# DSKY_control_circuitry.net
KiCad netlist of a schematic drawn in EAGLE
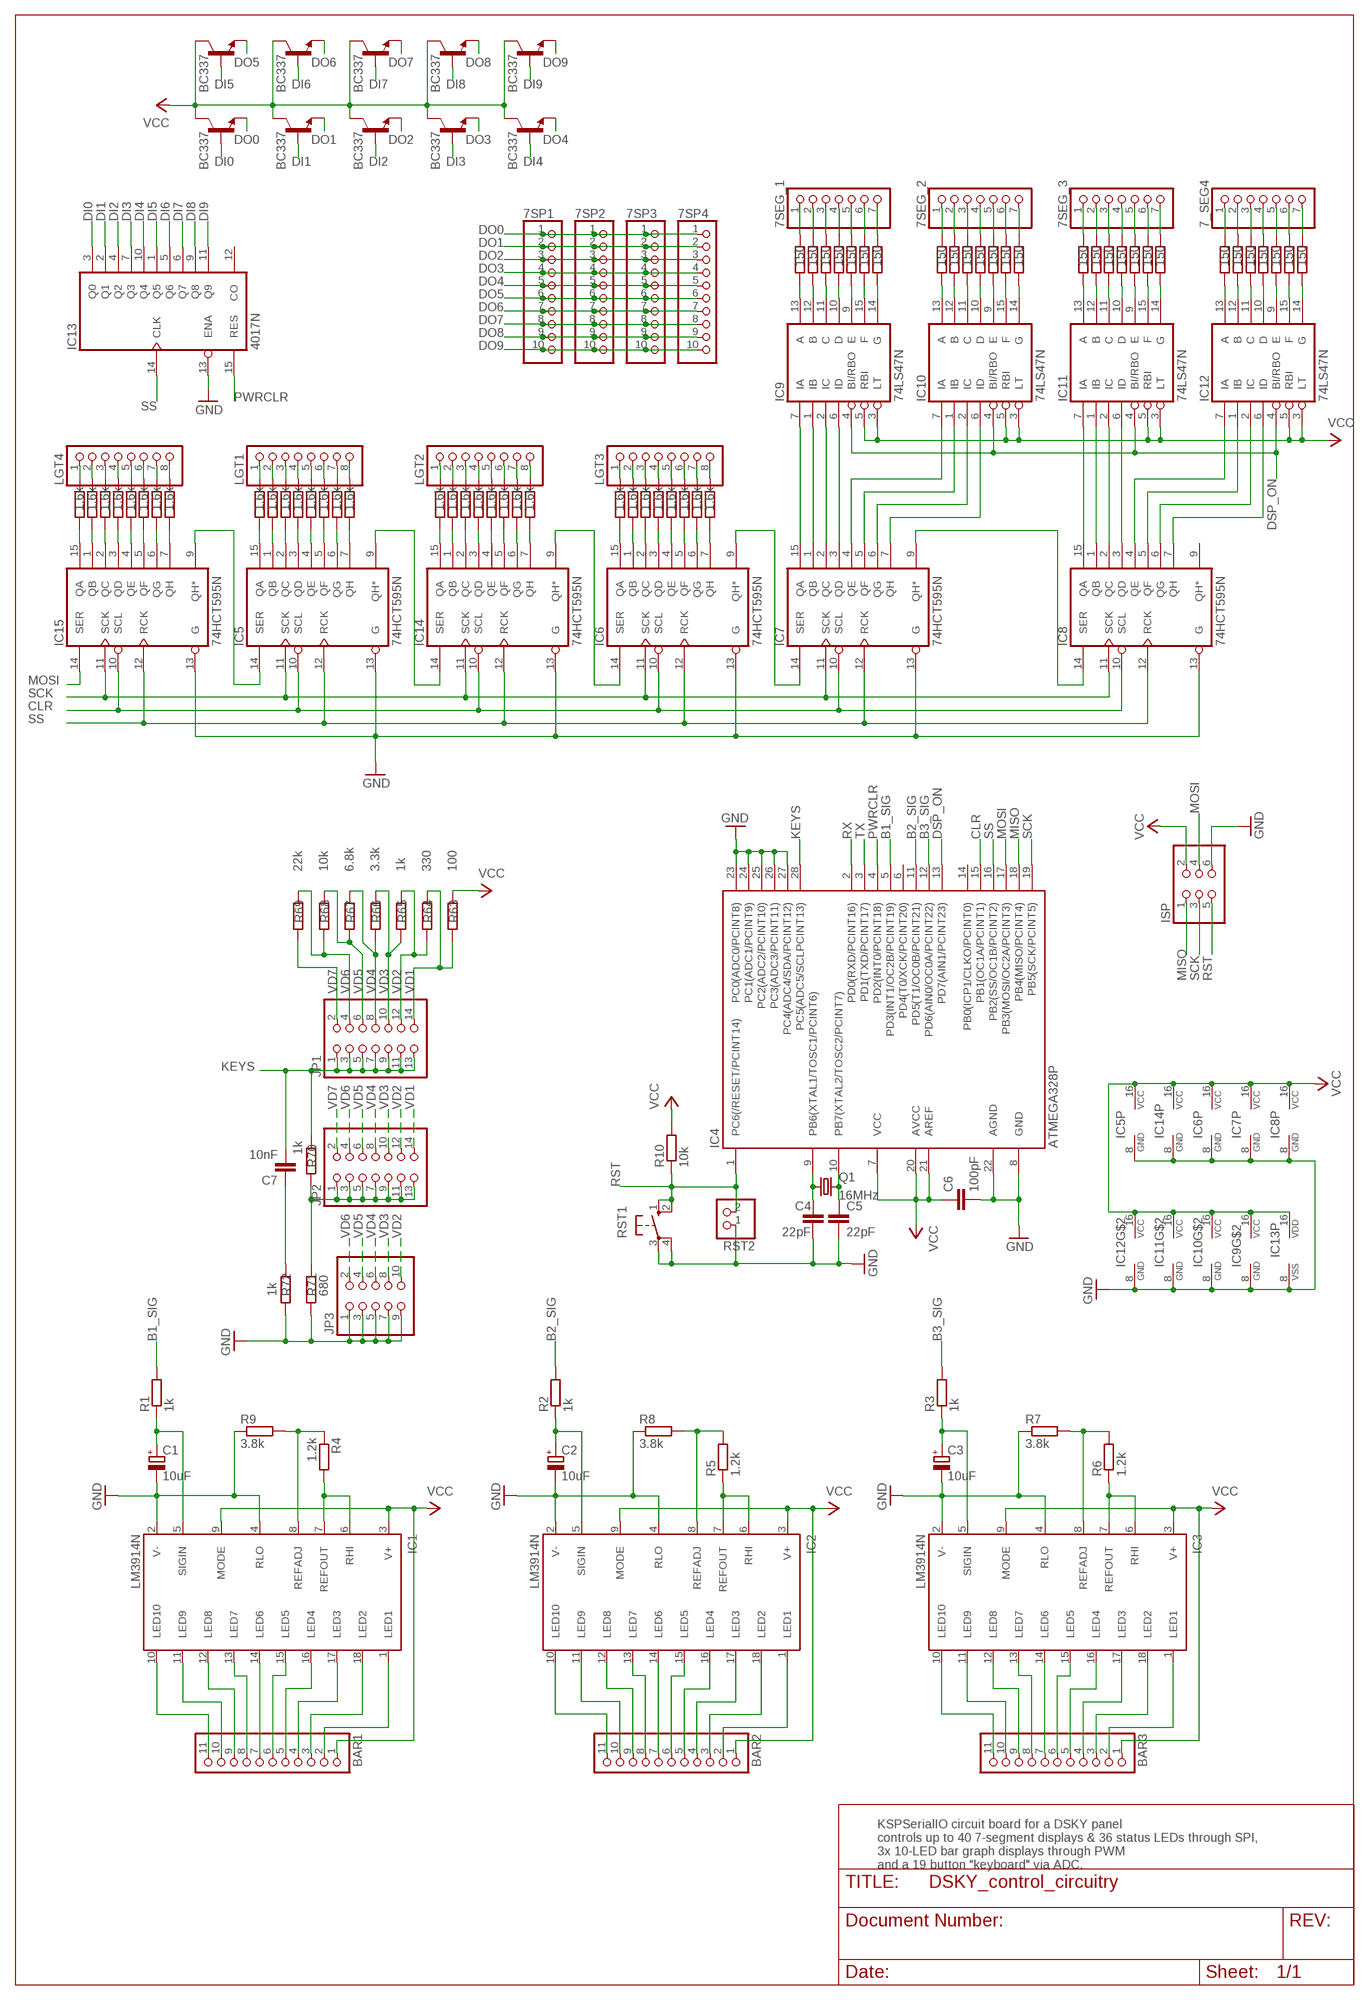
[diagram p0: schematic, sheet 1]

(export (version "E")
  (design (tool "Eeschema 10.0.6"))
  (components
    (comp (ref "7SEG_1")
      (value "PINHD-1X7")
      (footprint "eagle-import:1X07")
      (libsource (lib "eagle-import") (part "PINHD-1X7"))
    )
    (comp (ref "7SEG_2")
      (value "PINHD-1X7")
      (footprint "eagle-import:1X07")
      (libsource (lib "eagle-import") (part "PINHD-1X7"))
    )
    (comp (ref "7SEG_3")
      (value "PINHD-1X7")
      (footprint "eagle-import:1X07")
      (libsource (lib "eagle-import") (part "PINHD-1X7"))
    )
    (comp (ref "7SP1")
      (value "PINHD-1X10")
      (footprint "eagle-import:1X10")
      (libsource (lib "eagle-import") (part "PINHD-1X10"))
    )
    (comp (ref "7SP2")
      (value "PINHD-1X10")
      (footprint "eagle-import:1X10")
      (libsource (lib "eagle-import") (part "PINHD-1X10"))
    )
    (comp (ref "7SP3")
      (value "PINHD-1X10")
      (footprint "eagle-import:1X10")
      (libsource (lib "eagle-import") (part "PINHD-1X10"))
    )
    (comp (ref "7SP4")
      (value "PINHD-1X10")
      (footprint "eagle-import:1X10")
      (libsource (lib "eagle-import") (part "PINHD-1X10"))
    )
    (comp (ref "7_SEG4")
      (value "PINHD-1X7")
      (footprint "eagle-import:1X07")
      (libsource (lib "eagle-import") (part "PINHD-1X7"))
    )
    (comp (ref "BAR1")
      (value "PINHD-1X11")
      (footprint "eagle-import:1X11")
      (libsource (lib "eagle-import") (part "PINHD-1X11"))
    )
    (comp (ref "BAR2")
      (value "PINHD-1X11")
      (footprint "eagle-import:1X11")
      (libsource (lib "eagle-import") (part "PINHD-1X11"))
    )
    (comp (ref "BAR3")
      (value "PINHD-1X11")
      (footprint "eagle-import:1X11")
      (libsource (lib "eagle-import") (part "PINHD-1X11"))
    )
    (comp (ref "C1")
      (value "10uF")
      (footprint "eagle-import:E1,8-4")
      (libsource (lib "eagle-import") (part "CPOL-EUE1.8-4"))
    )
    (comp (ref "C2")
      (value "10uF")
      (footprint "eagle-import:E1,8-4")
      (libsource (lib "eagle-import") (part "CPOL-EUE1.8-4"))
    )
    (comp (ref "C3")
      (value "10uF")
      (footprint "eagle-import:E1,8-4")
      (libsource (lib "eagle-import") (part "CPOL-EUE1.8-4"))
    )
    (comp (ref "C4")
      (value "22pF")
      (footprint "eagle-import:C025-024X044")
      (libsource (lib "eagle-import") (part "C-EU025-024X044"))
    )
    (comp (ref "C5")
      (value "22pF")
      (footprint "eagle-import:C025-024X044")
      (libsource (lib "eagle-import") (part "C-EU025-024X044"))
    )
    (comp (ref "C6")
      (value "100pF")
      (footprint "eagle-import:C025-024X044")
      (libsource (lib "eagle-import") (part "C-EU025-024X044"))
    )
    (comp (ref "C7")
      (value "10nF")
      (footprint "eagle-import:C025-024X044")
      (libsource (lib "eagle-import") (part "C-EU025-024X044"))
    )
    (comp (ref "IC1")
      (value "LM3914N")
      (footprint "eagle-import:DIL18")
      (libsource (lib "eagle-import") (part "LM391N4"))
    )
    (comp (ref "IC2")
      (value "LM3914N")
      (footprint "eagle-import:DIL18")
      (libsource (lib "eagle-import") (part "LM391N4"))
    )
    (comp (ref "IC3")
      (value "LM3914N")
      (footprint "eagle-import:DIL18")
      (libsource (lib "eagle-import") (part "LM391N4"))
    )
    (comp (ref "IC4")
      (value "ATMEGA328P")
      (footprint "eagle-import:DIL28-3")
      (libsource (lib "eagle-import") (part "MEGA48/88/168-PU"))
    )
    (comp (ref "IC5")
      (value "74HCT595N")
      (footprint "eagle-import:DIL16")
      (libsource (lib "eagle-import") (part "74595NHCT"))
    )
    (comp (ref "IC6")
      (value "74HCT595N")
      (footprint "eagle-import:DIL16")
      (libsource (lib "eagle-import") (part "74595NHCT"))
    )
    (comp (ref "IC7")
      (value "74HCT595N")
      (footprint "eagle-import:DIL16")
      (libsource (lib "eagle-import") (part "74595NHCT"))
    )
    (comp (ref "IC8")
      (value "74HCT595N")
      (footprint "eagle-import:DIL16")
      (libsource (lib "eagle-import") (part "74595NHCT"))
    )
    (comp (ref "IC9")
      (value "74LS47N")
      (footprint "eagle-import:DIL16")
      (libsource (lib "eagle-import") (part "7447NLS"))
    )
    (comp (ref "IC10")
      (value "74LS47N")
      (footprint "eagle-import:DIL16")
      (libsource (lib "eagle-import") (part "7447NLS"))
    )
    (comp (ref "IC11")
      (value "74LS47N")
      (footprint "eagle-import:DIL16")
      (libsource (lib "eagle-import") (part "7447NLS"))
    )
    (comp (ref "IC12")
      (value "74LS47N")
      (footprint "eagle-import:DIL16")
      (libsource (lib "eagle-import") (part "7447NLS"))
    )
    (comp (ref "IC13")
      (value "4017N")
      (footprint "eagle-import:DIL16")
      (libsource (lib "eagle-import") (part "4017N"))
    )
    (comp (ref "IC14")
      (value "74HCT595N")
      (footprint "eagle-import:DIL16")
      (libsource (lib "eagle-import") (part "74595NHCT"))
    )
    (comp (ref "IC15")
      (value "74HCT595N")
      (footprint "eagle-import:DIL16")
      (libsource (lib "eagle-import") (part "74595NHCT"))
    )
    (comp (ref "ISP")
      (value "PINHD-2X3")
      (footprint "eagle-import:2X03")
      (libsource (lib "eagle-import") (part "PINHD-2X3"))
    )
    (comp (ref "JP1")
      (value "PINHD-2X7")
      (footprint "eagle-import:2X07")
      (libsource (lib "eagle-import") (part "PINHD-2X7"))
    )
    (comp (ref "JP2")
      (value "PINHD-2X7")
      (footprint "eagle-import:2X07")
      (libsource (lib "eagle-import") (part "PINHD-2X7"))
    )
    (comp (ref "JP3")
      (value "PINHD-2X5")
      (footprint "eagle-import:2X05")
      (libsource (lib "eagle-import") (part "PINHD-2X5"))
    )
    (comp (ref "LGT1")
      (value "PINHD-1X8")
      (footprint "eagle-import:1X08")
      (libsource (lib "eagle-import") (part "PINHD-1X8"))
    )
    (comp (ref "LGT2")
      (value "PINHD-1X8")
      (footprint "eagle-import:1X08")
      (libsource (lib "eagle-import") (part "PINHD-1X8"))
    )
    (comp (ref "LGT3")
      (value "PINHD-1X8")
      (footprint "eagle-import:1X08")
      (libsource (lib "eagle-import") (part "PINHD-1X8"))
    )
    (comp (ref "LGT4")
      (value "PINHD-1X8")
      (footprint "eagle-import:1X08")
      (libsource (lib "eagle-import") (part "PINHD-1X8"))
    )
    (comp (ref "Q1")
      (value "16MHz")
      (footprint "eagle-import:HC49_S")
      (libsource (lib "eagle-import") (part "CRYSTALHC49S"))
    )
    (comp (ref "Q2")
      (value "BC337")
      (footprint "eagle-import:TO92")
      (libsource (lib "eagle-import") (part "BC337"))
    )
    (comp (ref "Q3")
      (value "BC337")
      (footprint "eagle-import:TO92")
      (libsource (lib "eagle-import") (part "BC337"))
    )
    (comp (ref "Q4")
      (value "BC337")
      (footprint "eagle-import:TO92")
      (libsource (lib "eagle-import") (part "BC337"))
    )
    (comp (ref "Q5")
      (value "BC337")
      (footprint "eagle-import:TO92")
      (libsource (lib "eagle-import") (part "BC337"))
    )
    (comp (ref "Q6")
      (value "BC337")
      (footprint "eagle-import:TO92")
      (libsource (lib "eagle-import") (part "BC337"))
    )
    (comp (ref "Q7")
      (value "BC337")
      (footprint "eagle-import:TO92")
      (libsource (lib "eagle-import") (part "BC337"))
    )
    (comp (ref "Q8")
      (value "BC337")
      (footprint "eagle-import:TO92")
      (libsource (lib "eagle-import") (part "BC337"))
    )
    (comp (ref "Q9")
      (value "BC337")
      (footprint "eagle-import:TO92")
      (libsource (lib "eagle-import") (part "BC337"))
    )
    (comp (ref "Q10")
      (value "BC337")
      (footprint "eagle-import:TO92")
      (libsource (lib "eagle-import") (part "BC337"))
    )
    (comp (ref "Q11")
      (value "BC337")
      (footprint "eagle-import:TO92")
      (libsource (lib "eagle-import") (part "BC337"))
    )
    (comp (ref "R1")
      (value "1k")
      (footprint "eagle-import:0204V")
      (libsource (lib "eagle-import") (part "R-EU_0204/2V"))
    )
    (comp (ref "R2")
      (value "1k")
      (footprint "eagle-import:0204V")
      (libsource (lib "eagle-import") (part "R-EU_0204/2V"))
    )
    (comp (ref "R3")
      (value "1k")
      (footprint "eagle-import:0204V")
      (libsource (lib "eagle-import") (part "R-EU_0204/2V"))
    )
    (comp (ref "R4")
      (value "1.2k")
      (footprint "eagle-import:0204V")
      (libsource (lib "eagle-import") (part "R-EU_0204/2V"))
    )
    (comp (ref "R5")
      (value "1.2k")
      (footprint "eagle-import:0204V")
      (libsource (lib "eagle-import") (part "R-EU_0204/2V"))
    )
    (comp (ref "R6")
      (value "1.2k")
      (footprint "eagle-import:0204V")
      (libsource (lib "eagle-import") (part "R-EU_0204/2V"))
    )
    (comp (ref "R7")
      (value "3.8k")
      (footprint "eagle-import:0204V")
      (libsource (lib "eagle-import") (part "R-EU_0204/2V"))
    )
    (comp (ref "R8")
      (value "3.8k")
      (footprint "eagle-import:0204V")
      (libsource (lib "eagle-import") (part "R-EU_0204/2V"))
    )
    (comp (ref "R9")
      (value "3.8k")
      (footprint "eagle-import:0204V")
      (libsource (lib "eagle-import") (part "R-EU_0204/2V"))
    )
    (comp (ref "R10")
      (value "10k")
      (footprint "eagle-import:0204V")
      (libsource (lib "eagle-import") (part "R-EU_0204/2V"))
    )
    (comp (ref "R11")
      (value "150")
      (footprint "eagle-import:0204V")
      (libsource (lib "eagle-import") (part "R-EU_0204/2V"))
    )
    (comp (ref "R12")
      (value "150")
      (footprint "eagle-import:0204V")
      (libsource (lib "eagle-import") (part "R-EU_0204/2V"))
    )
    (comp (ref "R13")
      (value "150")
      (footprint "eagle-import:0204V")
      (libsource (lib "eagle-import") (part "R-EU_0204/2V"))
    )
    (comp (ref "R14")
      (value "150")
      (footprint "eagle-import:0204V")
      (libsource (lib "eagle-import") (part "R-EU_0204/2V"))
    )
    (comp (ref "R15")
      (value "150")
      (footprint "eagle-import:0204V")
      (libsource (lib "eagle-import") (part "R-EU_0204/2V"))
    )
    (comp (ref "R16")
      (value "150")
      (footprint "eagle-import:0204V")
      (libsource (lib "eagle-import") (part "R-EU_0204/2V"))
    )
    (comp (ref "R17")
      (value "150")
      (footprint "eagle-import:0204V")
      (libsource (lib "eagle-import") (part "R-EU_0204/2V"))
    )
    (comp (ref "R18")
      (value "150")
      (footprint "eagle-import:0204V")
      (libsource (lib "eagle-import") (part "R-EU_0204/2V"))
    )
    (comp (ref "R19")
      (value "150")
      (footprint "eagle-import:0204V")
      (libsource (lib "eagle-import") (part "R-EU_0204/2V"))
    )
    (comp (ref "R20")
      (value "150")
      (footprint "eagle-import:0204V")
      (libsource (lib "eagle-import") (part "R-EU_0204/2V"))
    )
    (comp (ref "R21")
      (value "150")
      (footprint "eagle-import:0204V")
      (libsource (lib "eagle-import") (part "R-EU_0204/2V"))
    )
    (comp (ref "R22")
      (value "150")
      (footprint "eagle-import:0204V")
      (libsource (lib "eagle-import") (part "R-EU_0204/2V"))
    )
    (comp (ref "R23")
      (value "150")
      (footprint "eagle-import:0204V")
      (libsource (lib "eagle-import") (part "R-EU_0204/2V"))
    )
    (comp (ref "R24")
      (value "150")
      (footprint "eagle-import:0204V")
      (libsource (lib "eagle-import") (part "R-EU_0204/2V"))
    )
    (comp (ref "R25")
      (value "150")
      (footprint "eagle-import:0204V")
      (libsource (lib "eagle-import") (part "R-EU_0204/2V"))
    )
    (comp (ref "R26")
      (value "150")
      (footprint "eagle-import:0204V")
      (libsource (lib "eagle-import") (part "R-EU_0204/2V"))
    )
    (comp (ref "R27")
      (value "150")
      (footprint "eagle-import:0204V")
      (libsource (lib "eagle-import") (part "R-EU_0204/2V"))
    )
    (comp (ref "R28")
      (value "150")
      (footprint "eagle-import:0204V")
      (libsource (lib "eagle-import") (part "R-EU_0204/2V"))
    )
    (comp (ref "R29")
      (value "150")
      (footprint "eagle-import:0204V")
      (libsource (lib "eagle-import") (part "R-EU_0204/2V"))
    )
    (comp (ref "R30")
      (value "150")
      (footprint "eagle-import:0204V")
      (libsource (lib "eagle-import") (part "R-EU_0204/2V"))
    )
    (comp (ref "R31")
      (value "150")
      (footprint "eagle-import:0204V")
      (libsource (lib "eagle-import") (part "R-EU_0204/2V"))
    )
    (comp (ref "R32")
      (value "150")
      (footprint "eagle-import:0204V")
      (libsource (lib "eagle-import") (part "R-EU_0204/2V"))
    )
    (comp (ref "R33")
      (value "150")
      (footprint "eagle-import:0204V")
      (libsource (lib "eagle-import") (part "R-EU_0204/2V"))
    )
    (comp (ref "R34")
      (value "150")
      (footprint "eagle-import:0204V")
      (libsource (lib "eagle-import") (part "R-EU_0204/2V"))
    )
    (comp (ref "R35")
      (value "150")
      (footprint "eagle-import:0204V")
      (libsource (lib "eagle-import") (part "R-EU_0204/2V"))
    )
    (comp (ref "R36")
      (value "150")
      (footprint "eagle-import:0204V")
      (libsource (lib "eagle-import") (part "R-EU_0204/2V"))
    )
    (comp (ref "R37")
      (value "150")
      (footprint "eagle-import:0204V")
      (libsource (lib "eagle-import") (part "R-EU_0204/2V"))
    )
    (comp (ref "R38")
      (value "150")
      (footprint "eagle-import:0204V")
      (libsource (lib "eagle-import") (part "R-EU_0204/2V"))
    )
    (comp (ref "R39")
      (value "1.6k")
      (footprint "eagle-import:0204V")
      (libsource (lib "eagle-import") (part "R-EU_0204/2V"))
    )
    (comp (ref "R40")
      (value "1.6k")
      (footprint "eagle-import:0204V")
      (libsource (lib "eagle-import") (part "R-EU_0204/2V"))
    )
    (comp (ref "R41")
      (value "1.6k")
      (footprint "eagle-import:0204V")
      (libsource (lib "eagle-import") (part "R-EU_0204/2V"))
    )
    (comp (ref "R42")
      (value "1.6k")
      (footprint "eagle-import:0204V")
      (libsource (lib "eagle-import") (part "R-EU_0204/2V"))
    )
    (comp (ref "R43")
      (value "1.6k")
      (footprint "eagle-import:0204V")
      (libsource (lib "eagle-import") (part "R-EU_0204/2V"))
    )
    (comp (ref "R44")
      (value "1.6k")
      (footprint "eagle-import:0204V")
      (libsource (lib "eagle-import") (part "R-EU_0204/2V"))
    )
    (comp (ref "R45")
      (value "1.6k")
      (footprint "eagle-import:0204V")
      (libsource (lib "eagle-import") (part "R-EU_0204/2V"))
    )
    (comp (ref "R46")
      (value "1.6k")
      (footprint "eagle-import:0204V")
      (libsource (lib "eagle-import") (part "R-EU_0204/2V"))
    )
    (comp (ref "R47")
      (value "1.6k")
      (footprint "eagle-import:0204V")
      (libsource (lib "eagle-import") (part "R-EU_0204/2V"))
    )
    (comp (ref "R48")
      (value "1.6k")
      (footprint "eagle-import:0204V")
      (libsource (lib "eagle-import") (part "R-EU_0204/2V"))
    )
    (comp (ref "R49")
      (value "1.6k")
      (footprint "eagle-import:0204V")
      (libsource (lib "eagle-import") (part "R-EU_0204/2V"))
    )
    (comp (ref "R50")
      (value "1.6k")
      (footprint "eagle-import:0204V")
      (libsource (lib "eagle-import") (part "R-EU_0204/2V"))
    )
    (comp (ref "R51")
      (value "1.6k")
      (footprint "eagle-import:0204V")
      (libsource (lib "eagle-import") (part "R-EU_0204/2V"))
    )
    (comp (ref "R52")
      (value "1.6k")
      (footprint "eagle-import:0204V")
      (libsource (lib "eagle-import") (part "R-EU_0204/2V"))
    )
    (comp (ref "R53")
      (value "1.6k")
      (footprint "eagle-import:0204V")
      (libsource (lib "eagle-import") (part "R-EU_0204/2V"))
    )
    (comp (ref "R54")
      (value "1.6k")
      (footprint "eagle-import:0204V")
      (libsource (lib "eagle-import") (part "R-EU_0204/2V"))
    )
    (comp (ref "R55")
      (value "1.6k")
      (footprint "eagle-import:0204V")
      (libsource (lib "eagle-import") (part "R-EU_0204/2V"))
    )
    (comp (ref "R56")
      (value "1.6k")
      (footprint "eagle-import:0204V")
      (libsource (lib "eagle-import") (part "R-EU_0204/2V"))
    )
    (comp (ref "R57")
      (value "1.6k")
      (footprint "eagle-import:0204V")
      (libsource (lib "eagle-import") (part "R-EU_0204/2V"))
    )
    (comp (ref "R58")
      (value "1.6k")
      (footprint "eagle-import:0204V")
      (libsource (lib "eagle-import") (part "R-EU_0204/2V"))
    )
    (comp (ref "R59")
      (value "1.6k")
      (footprint "eagle-import:0204V")
      (libsource (lib "eagle-import") (part "R-EU_0204/2V"))
    )
    (comp (ref "R60")
      (value "1.6k")
      (footprint "eagle-import:0204V")
      (libsource (lib "eagle-import") (part "R-EU_0204/2V"))
    )
    (comp (ref "R61")
      (value "1.6k")
      (footprint "eagle-import:0204V")
      (libsource (lib "eagle-import") (part "R-EU_0204/2V"))
    )
    (comp (ref "R62")
      (value "1.6k")
      (footprint "eagle-import:0204V")
      (libsource (lib "eagle-import") (part "R-EU_0204/2V"))
    )
    (comp (ref "R63")
      (value "100")
      (footprint "eagle-import:0204V")
      (libsource (lib "eagle-import") (part "R-EU_0204/2V"))
    )
    (comp (ref "R64")
      (value "330")
      (footprint "eagle-import:0204V")
      (libsource (lib "eagle-import") (part "R-EU_0204/2V"))
    )
    (comp (ref "R65")
      (value "1k")
      (footprint "eagle-import:0204V")
      (libsource (lib "eagle-import") (part "R-EU_0204/2V"))
    )
    (comp (ref "R66")
      (value "3.3k")
      (footprint "eagle-import:0204V")
      (libsource (lib "eagle-import") (part "R-EU_0204/2V"))
    )
    (comp (ref "R67")
      (value "6.8k")
      (footprint "eagle-import:0204V")
      (libsource (lib "eagle-import") (part "R-EU_0204/2V"))
    )
    (comp (ref "R68")
      (value "10k")
      (footprint "eagle-import:0204V")
      (libsource (lib "eagle-import") (part "R-EU_0204/2V"))
    )
    (comp (ref "R69")
      (value "22k")
      (footprint "eagle-import:0204V")
      (libsource (lib "eagle-import") (part "R-EU_0204/2V"))
    )
    (comp (ref "R70")
      (value "1k")
      (footprint "eagle-import:0204V")
      (libsource (lib "eagle-import") (part "R-EU_0204/2V"))
    )
    (comp (ref "R71")
      (value "680")
      (footprint "eagle-import:0204V")
      (libsource (lib "eagle-import") (part "R-EU_0204/2V"))
    )
    (comp (ref "R72")
      (value "1k")
      (footprint "eagle-import:0204V")
      (libsource (lib "eagle-import") (part "R-EU_0204/2V"))
    )
    (comp (ref "R73")
      (value "1.6k")
      (footprint "eagle-import:0204V")
      (libsource (lib "eagle-import") (part "R-EU_0204/2V"))
    )
    (comp (ref "R74")
      (value "1.6k")
      (footprint "eagle-import:0204V")
      (libsource (lib "eagle-import") (part "R-EU_0204/2V"))
    )
    (comp (ref "R75")
      (value "1.6k")
      (footprint "eagle-import:0204V")
      (libsource (lib "eagle-import") (part "R-EU_0204/2V"))
    )
    (comp (ref "R76")
      (value "1.6k")
      (footprint "eagle-import:0204V")
      (libsource (lib "eagle-import") (part "R-EU_0204/2V"))
    )
    (comp (ref "R77")
      (value "1.6k")
      (footprint "eagle-import:0204V")
      (libsource (lib "eagle-import") (part "R-EU_0204/2V"))
    )
    (comp (ref "R78")
      (value "1.6k")
      (footprint "eagle-import:0204V")
      (libsource (lib "eagle-import") (part "R-EU_0204/2V"))
    )
    (comp (ref "R79")
      (value "1.6k")
      (footprint "eagle-import:0204V")
      (libsource (lib "eagle-import") (part "R-EU_0204/2V"))
    )
    (comp (ref "R80")
      (value "1.6k")
      (footprint "eagle-import:0204V")
      (libsource (lib "eagle-import") (part "R-EU_0204/2V"))
    )
    (comp (ref "RST1")
      (value "10-XX")
      (footprint "eagle-import:B3F-10XX")
      (fields (field (name "MPN") "B3F-1000"))
      (libsource (lib "eagle-import") (part "10-XX"))
    )
    (comp (ref "RST2")
      (value "PINHD-1X2")
      (footprint "eagle-import:1X02")
      (libsource (lib "eagle-import") (part "PINHD-1X2"))
    )
  )
  (nets
    (net (code "1") (name "/B1_SIG") (class "Default")
      (node (ref "IC4") (pin "5") (pinfunction "PD3(INT1/OC2B/PCINT19)_5") (pintype "bidirectional"))
      (node (ref "R1") (pin "2") (pinfunction "2_2") (pintype "passive"))
    )
    (net (code "2") (name "/B2_SIG") (class "Default")
      (node (ref "IC4") (pin "11") (pinfunction "PD5(T1/OC0B/PCINT21)_11") (pintype "bidirectional"))
      (node (ref "R2") (pin "2") (pinfunction "2_2") (pintype "passive"))
    )
    (net (code "3") (name "/B3_SIG") (class "Default")
      (node (ref "IC4") (pin "12") (pinfunction "PD6(AIN0/OC0A/PCINT22)_12") (pintype "bidirectional"))
      (node (ref "R3") (pin "2") (pinfunction "2_2") (pintype "passive"))
    )
    (net (code "4") (name "/CLR") (class "Default")
      (node (ref "IC14") (pin "10") (pinfunction "SCL_10") (pintype "input"))
      (node (ref "IC15") (pin "10") (pinfunction "SCL_10") (pintype "input"))
      (node (ref "IC4") (pin "15") (pinfunction "PB1(OC1A/PCINT1)_15") (pintype "bidirectional"))
      (node (ref "IC5") (pin "10") (pinfunction "SCL_10") (pintype "input"))
      (node (ref "IC6") (pin "10") (pinfunction "SCL_10") (pintype "input"))
      (node (ref "IC7") (pin "10") (pinfunction "SCL_10") (pintype "input"))
      (node (ref "IC8") (pin "10") (pinfunction "SCL_10") (pintype "input"))
    )
    (net (code "5") (name "/DI0") (class "Default")
      (node (ref "IC13") (pin "3") (pinfunction "Q0_3") (pintype "output"))
      (node (ref "Q2") (pin "2") (pinfunction "B_2") (pintype "passive"))
    )
    (net (code "6") (name "/DI1") (class "Default")
      (node (ref "IC13") (pin "2") (pinfunction "Q1_2") (pintype "output"))
      (node (ref "Q3") (pin "2") (pinfunction "B_2") (pintype "passive"))
    )
    (net (code "7") (name "/DI2") (class "Default")
      (node (ref "IC13") (pin "4") (pinfunction "Q2_4") (pintype "output"))
      (node (ref "Q4") (pin "2") (pinfunction "B_2") (pintype "passive"))
    )
    (net (code "8") (name "/DI3") (class "Default")
      (node (ref "IC13") (pin "7") (pinfunction "Q3_7") (pintype "output"))
      (node (ref "Q5") (pin "2") (pinfunction "B_2") (pintype "passive"))
    )
    (net (code "9") (name "/DI4") (class "Default")
      (node (ref "IC13") (pin "10") (pinfunction "Q4_10") (pintype "output"))
      (node (ref "Q6") (pin "2") (pinfunction "B_2") (pintype "passive"))
    )
    (net (code "10") (name "/DI5") (class "Default")
      (node (ref "IC13") (pin "1") (pinfunction "Q5_1") (pintype "output"))
      (node (ref "Q7") (pin "2") (pinfunction "B_2") (pintype "passive"))
    )
    (net (code "11") (name "/DI6") (class "Default")
      (node (ref "IC13") (pin "5") (pinfunction "Q6_5") (pintype "output"))
      (node (ref "Q8") (pin "2") (pinfunction "B_2") (pintype "passive"))
    )
    (net (code "12") (name "/DI7") (class "Default")
      (node (ref "IC13") (pin "6") (pinfunction "Q7_6") (pintype "output"))
      (node (ref "Q9") (pin "2") (pinfunction "B_2") (pintype "passive"))
    )
    (net (code "13") (name "/DI8") (class "Default")
      (node (ref "IC13") (pin "9") (pinfunction "Q8_9") (pintype "output"))
      (node (ref "Q10") (pin "2") (pinfunction "B_2") (pintype "passive"))
    )
    (net (code "14") (name "/DI9") (class "Default")
      (node (ref "IC13") (pin "11") (pinfunction "Q9_11") (pintype "output"))
      (node (ref "Q11") (pin "2") (pinfunction "B_2") (pintype "passive"))
    )
    (net (code "15") (name "/DO0") (class "Default")
      (node (ref "7SP1") (pin "1") (pinfunction "1_1") (pintype "passive"))
      (node (ref "7SP2") (pin "1") (pinfunction "1_1") (pintype "passive"))
      (node (ref "7SP3") (pin "1") (pinfunction "1_1") (pintype "passive"))
      (node (ref "7SP4") (pin "1") (pinfunction "1_1") (pintype "passive"))
      (node (ref "Q2") (pin "1") (pinfunction "E_1") (pintype "passive"))
    )
    (net (code "16") (name "/DO1") (class "Default")
      (node (ref "7SP1") (pin "2") (pinfunction "2_2") (pintype "passive"))
      (node (ref "7SP2") (pin "2") (pinfunction "2_2") (pintype "passive"))
      (node (ref "7SP3") (pin "2") (pinfunction "2_2") (pintype "passive"))
      (node (ref "7SP4") (pin "2") (pinfunction "2_2") (pintype "passive"))
      (node (ref "Q3") (pin "1") (pinfunction "E_1") (pintype "passive"))
    )
    (net (code "17") (name "/DO2") (class "Default")
      (node (ref "7SP1") (pin "3") (pinfunction "3_3") (pintype "passive"))
      (node (ref "7SP2") (pin "3") (pinfunction "3_3") (pintype "passive"))
      (node (ref "7SP3") (pin "3") (pinfunction "3_3") (pintype "passive"))
      (node (ref "7SP4") (pin "3") (pinfunction "3_3") (pintype "passive"))
      (node (ref "Q4") (pin "1") (pinfunction "E_1") (pintype "passive"))
    )
    (net (code "18") (name "/DO3") (class "Default")
      (node (ref "7SP1") (pin "4") (pinfunction "4_4") (pintype "passive"))
      (node (ref "7SP2") (pin "4") (pinfunction "4_4") (pintype "passive"))
      (node (ref "7SP3") (pin "4") (pinfunction "4_4") (pintype "passive"))
      (node (ref "7SP4") (pin "4") (pinfunction "4_4") (pintype "passive"))
      (node (ref "Q5") (pin "1") (pinfunction "E_1") (pintype "passive"))
    )
    (net (code "19") (name "/DO4") (class "Default")
      (node (ref "7SP1") (pin "5") (pinfunction "5_5") (pintype "passive"))
      (node (ref "7SP2") (pin "5") (pinfunction "5_5") (pintype "passive"))
      (node (ref "7SP3") (pin "5") (pinfunction "5_5") (pintype "passive"))
      (node (ref "7SP4") (pin "5") (pinfunction "5_5") (pintype "passive"))
      (node (ref "Q6") (pin "1") (pinfunction "E_1") (pintype "passive"))
    )
    (net (code "20") (name "/DO5") (class "Default")
      (node (ref "7SP1") (pin "6") (pinfunction "6_6") (pintype "passive"))
      (node (ref "7SP2") (pin "6") (pinfunction "6_6") (pintype "passive"))
      (node (ref "7SP3") (pin "6") (pinfunction "6_6") (pintype "passive"))
      (node (ref "7SP4") (pin "6") (pinfunction "6_6") (pintype "passive"))
      (node (ref "Q7") (pin "1") (pinfunction "E_1") (pintype "passive"))
    )
    (net (code "21") (name "/DO6") (class "Default")
      (node (ref "7SP1") (pin "7") (pinfunction "7_7") (pintype "passive"))
      (node (ref "7SP2") (pin "7") (pinfunction "7_7") (pintype "passive"))
      (node (ref "7SP3") (pin "7") (pinfunction "7_7") (pintype "passive"))
      (node (ref "7SP4") (pin "7") (pinfunction "7_7") (pintype "passive"))
      (node (ref "Q8") (pin "1") (pinfunction "E_1") (pintype "passive"))
    )
    (net (code "22") (name "/DO7") (class "Default")
      (node (ref "7SP1") (pin "8") (pinfunction "8_8") (pintype "passive"))
      (node (ref "7SP2") (pin "8") (pinfunction "8_8") (pintype "passive"))
      (node (ref "7SP3") (pin "8") (pinfunction "8_8") (pintype "passive"))
      (node (ref "7SP4") (pin "8") (pinfunction "8_8") (pintype "passive"))
      (node (ref "Q9") (pin "1") (pinfunction "E_1") (pintype "passive"))
    )
    (net (code "23") (name "/DO8") (class "Default")
      (node (ref "7SP1") (pin "9") (pinfunction "9_9") (pintype "passive"))
      (node (ref "7SP2") (pin "9") (pinfunction "9_9") (pintype "passive"))
      (node (ref "7SP3") (pin "9") (pinfunction "9_9") (pintype "passive"))
      (node (ref "7SP4") (pin "9") (pinfunction "9_9") (pintype "passive"))
      (node (ref "Q10") (pin "1") (pinfunction "E_1") (pintype "passive"))
    )
    (net (code "24") (name "/DO9") (class "Default")
      (node (ref "7SP1") (pin "10") (pinfunction "10_10") (pintype "passive"))
      (node (ref "7SP2") (pin "10") (pinfunction "10_10") (pintype "passive"))
      (node (ref "7SP3") (pin "10") (pinfunction "10_10") (pintype "passive"))
      (node (ref "7SP4") (pin "10") (pinfunction "10_10") (pintype "passive"))
      (node (ref "Q11") (pin "1") (pinfunction "E_1") (pintype "passive"))
    )
    (net (code "25") (name "/DSP_ON") (class "Default")
      (node (ref "IC10") (pin "4") (pinfunction "BI/RBO_4") (pintype "input"))
      (node (ref "IC11") (pin "4") (pinfunction "BI/RBO_4") (pintype "input"))
      (node (ref "IC12") (pin "4") (pinfunction "BI/RBO_4") (pintype "input"))
      (node (ref "IC4") (pin "13") (pinfunction "PD7(AIN1/PCINT23)_13") (pintype "bidirectional"))
      (node (ref "IC9") (pin "4") (pinfunction "BI/RBO_4") (pintype "input"))
    )
    (net (code "26") (name "/KEYS") (class "Default")
      (node (ref "C7") (pin "2") (pinfunction "2_2") (pintype "passive"))
      (node (ref "IC4") (pin "28") (pinfunction "PC5(ADC5/SCLPCINT13)_28") (pintype "bidirectional"))
      (node (ref "JP1") (pin "1") (pinfunction "1_1") (pintype "passive"))
      (node (ref "JP1") (pin "11") (pinfunction "11_11") (pintype "passive"))
      (node (ref "JP1") (pin "13") (pinfunction "13_13") (pintype "passive"))
      (node (ref "JP1") (pin "3") (pinfunction "3_3") (pintype "passive"))
      (node (ref "JP1") (pin "5") (pinfunction "5_5") (pintype "passive"))
      (node (ref "JP1") (pin "7") (pinfunction "7_7") (pintype "passive"))
      (node (ref "JP1") (pin "9") (pinfunction "9_9") (pintype "passive"))
      (node (ref "R70") (pin "2") (pinfunction "2_2") (pintype "passive"))
    )
    (net (code "27") (name "/MISO") (class "Default")
      (node (ref "IC4") (pin "18") (pinfunction "PB4(MISO/PCINT4)_18") (pintype "bidirectional"))
      (node (ref "ISP") (pin "1") (pinfunction "1_1") (pintype "passive"))
    )
    (net (code "28") (name "/MOSI") (class "Default")
      (node (ref "IC15") (pin "14") (pinfunction "SER_14") (pintype "input"))
      (node (ref "IC4") (pin "17") (pinfunction "PB3(MOSI/OC2A/PCINT3)_17") (pintype "bidirectional"))
      (node (ref "ISP") (pin "4") (pinfunction "4_4") (pintype "passive"))
    )
    (net (code "29") (name "/PWRCLR") (class "Default")
      (node (ref "IC13") (pin "15") (pinfunction "RES_15") (pintype "input"))
      (node (ref "IC4") (pin "4") (pinfunction "PD2(INT0/PCINT18)_4") (pintype "bidirectional"))
    )
    (net (code "30") (name "/RST") (class "Default")
      (node (ref "IC4") (pin "1") (pinfunction "PC6(/RESET/PCINT14)_1") (pintype "bidirectional"))
      (node (ref "ISP") (pin "5") (pinfunction "5_5") (pintype "passive"))
      (node (ref "R10") (pin "1") (pinfunction "1_1") (pintype "passive"))
      (node (ref "RST1") (pin "1") (pinfunction "S_1") (pintype "passive"))
      (node (ref "RST1") (pin "2") (pinfunction "S1_2") (pintype "passive"))
      (node (ref "RST2") (pin "2") (pinfunction "2_2") (pintype "passive"))
    )
    (net (code "31") (name "/RX") (class "Default")
      (node (ref "IC4") (pin "2") (pinfunction "PD0(RXD/PCINT16)_2") (pintype "bidirectional"))
    )
    (net (code "32") (name "/SCK") (class "Default")
      (node (ref "IC14") (pin "11") (pinfunction "SCK_11") (pintype "input"))
      (node (ref "IC15") (pin "11") (pinfunction "SCK_11") (pintype "input"))
      (node (ref "IC4") (pin "19") (pinfunction "PB5(SCK/PCINT5)_19") (pintype "bidirectional"))
      (node (ref "IC5") (pin "11") (pinfunction "SCK_11") (pintype "input"))
      (node (ref "IC6") (pin "11") (pinfunction "SCK_11") (pintype "input"))
      (node (ref "IC7") (pin "11") (pinfunction "SCK_11") (pintype "input"))
      (node (ref "IC8") (pin "11") (pinfunction "SCK_11") (pintype "input"))
      (node (ref "ISP") (pin "3") (pinfunction "3_3") (pintype "passive"))
    )
    (net (code "33") (name "/SS") (class "Default")
      (node (ref "IC13") (pin "14") (pinfunction "CLK_14") (pintype "input"))
      (node (ref "IC14") (pin "12") (pinfunction "RCK_12") (pintype "input"))
      (node (ref "IC15") (pin "12") (pinfunction "RCK_12") (pintype "input"))
      (node (ref "IC4") (pin "16") (pinfunction "PB2(SS/OC1B/PCINT2)_16") (pintype "bidirectional"))
      (node (ref "IC5") (pin "12") (pinfunction "RCK_12") (pintype "input"))
      (node (ref "IC6") (pin "12") (pinfunction "RCK_12") (pintype "input"))
      (node (ref "IC7") (pin "12") (pinfunction "RCK_12") (pintype "input"))
      (node (ref "IC8") (pin "12") (pinfunction "RCK_12") (pintype "input"))
    )
    (net (code "34") (name "/TX") (class "Default")
      (node (ref "IC4") (pin "3") (pinfunction "PD1(TXD/PCINT17)_3") (pintype "bidirectional"))
    )
    (net (code "35") (name "/VD1") (class "Default")
      (node (ref "JP1") (pin "14") (pinfunction "14_14") (pintype "passive"))
      (node (ref "JP2") (pin "14") (pinfunction "14_14") (pintype "passive"))
      (node (ref "R63") (pin "1") (pinfunction "1_1") (pintype "passive"))
      (node (ref "R64") (pin "2") (pinfunction "2_2") (pintype "passive"))
    )
    (net (code "36") (name "/VD2") (class "Default")
      (node (ref "JP1") (pin "12") (pinfunction "12_12") (pintype "passive"))
      (node (ref "JP2") (pin "12") (pinfunction "12_12") (pintype "passive"))
      (node (ref "JP3") (pin "10") (pinfunction "10_10") (pintype "passive"))
      (node (ref "R64") (pin "1") (pinfunction "1_1") (pintype "passive"))
      (node (ref "R65") (pin "2") (pinfunction "2_2") (pintype "passive"))
    )
    (net (code "37") (name "/VD3") (class "Default")
      (node (ref "JP1") (pin "10") (pinfunction "10_10") (pintype "passive"))
      (node (ref "JP2") (pin "10") (pinfunction "10_10") (pintype "passive"))
      (node (ref "JP3") (pin "8") (pinfunction "8_8") (pintype "passive"))
      (node (ref "R65") (pin "1") (pinfunction "1_1") (pintype "passive"))
      (node (ref "R66") (pin "2") (pinfunction "2_2") (pintype "passive"))
    )
    (net (code "38") (name "/VD4") (class "Default")
      (node (ref "JP1") (pin "8") (pinfunction "8_8") (pintype "passive"))
      (node (ref "JP2") (pin "8") (pinfunction "8_8") (pintype "passive"))
      (node (ref "JP3") (pin "6") (pinfunction "6_6") (pintype "passive"))
      (node (ref "R66") (pin "1") (pinfunction "1_1") (pintype "passive"))
      (node (ref "R67") (pin "2") (pinfunction "2_2") (pintype "passive"))
    )
    (net (code "39") (name "/VD5") (class "Default")
      (node (ref "JP1") (pin "6") (pinfunction "6_6") (pintype "passive"))
      (node (ref "JP2") (pin "6") (pinfunction "6_6") (pintype "passive"))
      (node (ref "JP3") (pin "4") (pinfunction "4_4") (pintype "passive"))
      (node (ref "R67") (pin "1") (pinfunction "1_1") (pintype "passive"))
      (node (ref "R68") (pin "2") (pinfunction "2_2") (pintype "passive"))
    )
    (net (code "40") (name "/VD6") (class "Default")
      (node (ref "JP1") (pin "4") (pinfunction "4_4") (pintype "passive"))
      (node (ref "JP2") (pin "4") (pinfunction "4_4") (pintype "passive"))
      (node (ref "JP3") (pin "2") (pinfunction "2_2") (pintype "passive"))
      (node (ref "R68") (pin "1") (pinfunction "1_1") (pintype "passive"))
      (node (ref "R69") (pin "2") (pinfunction "2_2") (pintype "passive"))
    )
    (net (code "41") (name "/VD7") (class "Default")
      (node (ref "JP1") (pin "2") (pinfunction "2_2") (pintype "passive"))
      (node (ref "JP2") (pin "2") (pinfunction "2_2") (pintype "passive"))
      (node (ref "R69") (pin "1") (pinfunction "1_1") (pintype "passive"))
    )
    (net (code "42") (name "GND") (class "Default")
      (node (ref "C1") (pin "-") (pinfunction "-_-") (pintype "passive"))
      (node (ref "C2") (pin "-") (pinfunction "-_-") (pintype "passive"))
      (node (ref "C3") (pin "-") (pinfunction "-_-") (pintype "passive"))
      (node (ref "C4") (pin "2") (pinfunction "2_2") (pintype "passive"))
      (node (ref "C5") (pin "2") (pinfunction "2_2") (pintype "passive"))
      (node (ref "C6") (pin "2") (pinfunction "2_2") (pintype "passive"))
      (node (ref "IC1") (pin "2") (pinfunction "V-_2") (pintype "power_in"))
      (node (ref "IC1") (pin "4") (pinfunction "RLO_4") (pintype "input"))
      (node (ref "IC10") (pin "8") (pinfunction "GND_8") (pintype "power_in"))
      (node (ref "IC11") (pin "8") (pinfunction "GND_8") (pintype "power_in"))
      (node (ref "IC12") (pin "8") (pinfunction "GND_8") (pintype "power_in"))
      (node (ref "IC13") (pin "13") (pinfunction "ENA_13") (pintype "input"))
      (node (ref "IC13") (pin "8") (pinfunction "VSS_8") (pintype "power_in"))
      (node (ref "IC14") (pin "13") (pinfunction "G_13") (pintype "input"))
      (node (ref "IC14") (pin "8") (pinfunction "GND_8") (pintype "power_in"))
      (node (ref "IC15") (pin "13") (pinfunction "G_13") (pintype "input"))
      (node (ref "IC2") (pin "2") (pinfunction "V-_2") (pintype "power_in"))
      (node (ref "IC2") (pin "4") (pinfunction "RLO_4") (pintype "input"))
      (node (ref "IC3") (pin "2") (pinfunction "V-_2") (pintype "power_in"))
      (node (ref "IC3") (pin "4") (pinfunction "RLO_4") (pintype "input"))
      (node (ref "IC4") (pin "22") (pinfunction "AGND_22") (pintype "power_in"))
      (node (ref "IC4") (pin "23") (pinfunction "PC0(ADC0/PCINT8)_23") (pintype "bidirectional"))
      (node (ref "IC4") (pin "24") (pinfunction "PC1(ADC1/PCINT9)_24") (pintype "bidirectional"))
      (node (ref "IC4") (pin "25") (pinfunction "PC2(ADC2/PCINT10)_25") (pintype "bidirectional"))
      (node (ref "IC4") (pin "26") (pinfunction "PC3(ADC3/PCINT11)_26") (pintype "bidirectional"))
      (node (ref "IC4") (pin "27") (pinfunction "PC4(ADC4/SDA/PCINT12)_27") (pintype "bidirectional"))
      (node (ref "IC4") (pin "8") (pinfunction "GND_8") (pintype "power_in"))
      (node (ref "IC5") (pin "13") (pinfunction "G_13") (pintype "input"))
      (node (ref "IC5") (pin "8") (pinfunction "GND_8") (pintype "power_in"))
      (node (ref "IC6") (pin "13") (pinfunction "G_13") (pintype "input"))
      (node (ref "IC6") (pin "8") (pinfunction "GND_8") (pintype "power_in"))
      (node (ref "IC7") (pin "13") (pinfunction "G_13") (pintype "input"))
      (node (ref "IC7") (pin "8") (pinfunction "GND_8") (pintype "power_in"))
      (node (ref "IC8") (pin "13") (pinfunction "G_13") (pintype "input"))
      (node (ref "IC8") (pin "8") (pinfunction "GND_8") (pintype "power_in"))
      (node (ref "IC9") (pin "8") (pinfunction "GND_8") (pintype "power_in"))
      (node (ref "ISP") (pin "6") (pinfunction "6_6") (pintype "passive"))
      (node (ref "JP3") (pin "1") (pinfunction "1_1") (pintype "passive"))
      (node (ref "JP3") (pin "3") (pinfunction "3_3") (pintype "passive"))
      (node (ref "JP3") (pin "5") (pinfunction "5_5") (pintype "passive"))
      (node (ref "JP3") (pin "7") (pinfunction "7_7") (pintype "passive"))
      (node (ref "JP3") (pin "9") (pinfunction "9_9") (pintype "passive"))
      (node (ref "R7") (pin "1") (pinfunction "1_1") (pintype "passive"))
      (node (ref "R71") (pin "1") (pinfunction "1_1") (pintype "passive"))
      (node (ref "R72") (pin "1") (pinfunction "1_1") (pintype "passive"))
      (node (ref "R8") (pin "1") (pinfunction "1_1") (pintype "passive"))
      (node (ref "R9") (pin "1") (pinfunction "1_1") (pintype "passive"))
      (node (ref "RST1") (pin "3") (pinfunction "P_3") (pintype "passive"))
      (node (ref "RST1") (pin "4") (pinfunction "P1_4") (pintype "passive"))
      (node (ref "RST2") (pin "1") (pinfunction "1_1") (pintype "passive"))
    )
    (net (code "43") (name "Net-(7SEG_1-Pad1)") (class "Default")
      (node (ref "7SEG_1") (pin "1") (pinfunction "1_1") (pintype "passive"))
      (node (ref "R11") (pin "2") (pinfunction "2_2") (pintype "passive"))
    )
    (net (code "44") (name "Net-(7SEG_1-Pad2)") (class "Default")
      (node (ref "7SEG_1") (pin "2") (pinfunction "2_2") (pintype "passive"))
      (node (ref "R12") (pin "2") (pinfunction "2_2") (pintype "passive"))
    )
    (net (code "45") (name "Net-(7SEG_1-Pad3)") (class "Default")
      (node (ref "7SEG_1") (pin "3") (pinfunction "3_3") (pintype "passive"))
      (node (ref "R13") (pin "2") (pinfunction "2_2") (pintype "passive"))
    )
    (net (code "46") (name "Net-(7SEG_1-Pad4)") (class "Default")
      (node (ref "7SEG_1") (pin "4") (pinfunction "4_4") (pintype "passive"))
      (node (ref "R14") (pin "2") (pinfunction "2_2") (pintype "passive"))
    )
    (net (code "47") (name "Net-(7SEG_1-Pad5)") (class "Default")
      (node (ref "7SEG_1") (pin "5") (pinfunction "5_5") (pintype "passive"))
      (node (ref "R15") (pin "2") (pinfunction "2_2") (pintype "passive"))
    )
    (net (code "48") (name "Net-(7SEG_1-Pad6)") (class "Default")
      (node (ref "7SEG_1") (pin "6") (pinfunction "6_6") (pintype "passive"))
      (node (ref "R16") (pin "2") (pinfunction "2_2") (pintype "passive"))
    )
    (net (code "49") (name "Net-(7SEG_1-Pad7)") (class "Default")
      (node (ref "7SEG_1") (pin "7") (pinfunction "7_7") (pintype "passive"))
      (node (ref "R17") (pin "2") (pinfunction "2_2") (pintype "passive"))
    )
    (net (code "50") (name "Net-(7SEG_2-Pad1)") (class "Default")
      (node (ref "7SEG_2") (pin "1") (pinfunction "1_1") (pintype "passive"))
      (node (ref "R18") (pin "2") (pinfunction "2_2") (pintype "passive"))
    )
    (net (code "51") (name "Net-(7SEG_2-Pad2)") (class "Default")
      (node (ref "7SEG_2") (pin "2") (pinfunction "2_2") (pintype "passive"))
      (node (ref "R19") (pin "2") (pinfunction "2_2") (pintype "passive"))
    )
    (net (code "52") (name "Net-(7SEG_2-Pad3)") (class "Default")
      (node (ref "7SEG_2") (pin "3") (pinfunction "3_3") (pintype "passive"))
      (node (ref "R20") (pin "2") (pinfunction "2_2") (pintype "passive"))
    )
    (net (code "53") (name "Net-(7SEG_2-Pad4)") (class "Default")
      (node (ref "7SEG_2") (pin "4") (pinfunction "4_4") (pintype "passive"))
      (node (ref "R21") (pin "2") (pinfunction "2_2") (pintype "passive"))
    )
    (net (code "54") (name "Net-(7SEG_2-Pad5)") (class "Default")
      (node (ref "7SEG_2") (pin "5") (pinfunction "5_5") (pintype "passive"))
      (node (ref "R22") (pin "2") (pinfunction "2_2") (pintype "passive"))
    )
    (net (code "55") (name "Net-(7SEG_2-Pad6)") (class "Default")
      (node (ref "7SEG_2") (pin "6") (pinfunction "6_6") (pintype "passive"))
      (node (ref "R23") (pin "2") (pinfunction "2_2") (pintype "passive"))
    )
    (net (code "56") (name "Net-(7SEG_2-Pad7)") (class "Default")
      (node (ref "7SEG_2") (pin "7") (pinfunction "7_7") (pintype "passive"))
      (node (ref "R24") (pin "2") (pinfunction "2_2") (pintype "passive"))
    )
    (net (code "57") (name "Net-(7SEG_3-Pad1)") (class "Default")
      (node (ref "7SEG_3") (pin "1") (pinfunction "1_1") (pintype "passive"))
      (node (ref "R25") (pin "2") (pinfunction "2_2") (pintype "passive"))
    )
    (net (code "58") (name "Net-(7SEG_3-Pad2)") (class "Default")
      (node (ref "7SEG_3") (pin "2") (pinfunction "2_2") (pintype "passive"))
      (node (ref "R26") (pin "2") (pinfunction "2_2") (pintype "passive"))
    )
    (net (code "59") (name "Net-(7SEG_3-Pad3)") (class "Default")
      (node (ref "7SEG_3") (pin "3") (pinfunction "3_3") (pintype "passive"))
      (node (ref "R27") (pin "2") (pinfunction "2_2") (pintype "passive"))
    )
    (net (code "60") (name "Net-(7SEG_3-Pad4)") (class "Default")
      (node (ref "7SEG_3") (pin "4") (pinfunction "4_4") (pintype "passive"))
      (node (ref "R28") (pin "2") (pinfunction "2_2") (pintype "passive"))
    )
    (net (code "61") (name "Net-(7SEG_3-Pad5)") (class "Default")
      (node (ref "7SEG_3") (pin "5") (pinfunction "5_5") (pintype "passive"))
      (node (ref "R29") (pin "2") (pinfunction "2_2") (pintype "passive"))
    )
    (net (code "62") (name "Net-(7SEG_3-Pad6)") (class "Default")
      (node (ref "7SEG_3") (pin "6") (pinfunction "6_6") (pintype "passive"))
      (node (ref "R30") (pin "2") (pinfunction "2_2") (pintype "passive"))
    )
    (net (code "63") (name "Net-(7SEG_3-Pad7)") (class "Default")
      (node (ref "7SEG_3") (pin "7") (pinfunction "7_7") (pintype "passive"))
      (node (ref "R31") (pin "2") (pinfunction "2_2") (pintype "passive"))
    )
    (net (code "64") (name "Net-(7_SEG4-Pad1)") (class "Default")
      (node (ref "7_SEG4") (pin "1") (pinfunction "1_1") (pintype "passive"))
      (node (ref "R32") (pin "2") (pinfunction "2_2") (pintype "passive"))
    )
    (net (code "65") (name "Net-(7_SEG4-Pad2)") (class "Default")
      (node (ref "7_SEG4") (pin "2") (pinfunction "2_2") (pintype "passive"))
      (node (ref "R33") (pin "2") (pinfunction "2_2") (pintype "passive"))
    )
    (net (code "66") (name "Net-(7_SEG4-Pad3)") (class "Default")
      (node (ref "7_SEG4") (pin "3") (pinfunction "3_3") (pintype "passive"))
      (node (ref "R34") (pin "2") (pinfunction "2_2") (pintype "passive"))
    )
    (net (code "67") (name "Net-(7_SEG4-Pad4)") (class "Default")
      (node (ref "7_SEG4") (pin "4") (pinfunction "4_4") (pintype "passive"))
      (node (ref "R35") (pin "2") (pinfunction "2_2") (pintype "passive"))
    )
    (net (code "68") (name "Net-(7_SEG4-Pad5)") (class "Default")
      (node (ref "7_SEG4") (pin "5") (pinfunction "5_5") (pintype "passive"))
      (node (ref "R36") (pin "2") (pinfunction "2_2") (pintype "passive"))
    )
    (net (code "69") (name "Net-(7_SEG4-Pad6)") (class "Default")
      (node (ref "7_SEG4") (pin "6") (pinfunction "6_6") (pintype "passive"))
      (node (ref "R37") (pin "2") (pinfunction "2_2") (pintype "passive"))
    )
    (net (code "70") (name "Net-(7_SEG4-Pad7)") (class "Default")
      (node (ref "7_SEG4") (pin "7") (pinfunction "7_7") (pintype "passive"))
      (node (ref "R38") (pin "2") (pinfunction "2_2") (pintype "passive"))
    )
    (net (code "71") (name "Net-(C7-Pad1)") (class "Default")
      (node (ref "C7") (pin "1") (pinfunction "1_1") (pintype "passive"))
      (node (ref "R72") (pin "2") (pinfunction "2_2") (pintype "passive"))
    )
    (net (code "72") (name "Net-(IC1-LED1)") (class "Default")
      (node (ref "BAR1") (pin "2") (pinfunction "2_2") (pintype "passive"))
      (node (ref "IC1") (pin "1") (pinfunction "LED1_1") (pintype "output"))
    )
    (net (code "73") (name "Net-(IC1-LED2)") (class "Default")
      (node (ref "BAR1") (pin "3") (pinfunction "3_3") (pintype "passive"))
      (node (ref "IC1") (pin "18") (pinfunction "LED2_18") (pintype "output"))
    )
    (net (code "74") (name "Net-(IC1-LED3)") (class "Default")
      (node (ref "BAR1") (pin "4") (pinfunction "4_4") (pintype "passive"))
      (node (ref "IC1") (pin "17") (pinfunction "LED3_17") (pintype "output"))
    )
    (net (code "75") (name "Net-(IC1-LED4)") (class "Default")
      (node (ref "BAR1") (pin "5") (pinfunction "5_5") (pintype "passive"))
      (node (ref "IC1") (pin "16") (pinfunction "LED4_16") (pintype "output"))
    )
    (net (code "76") (name "Net-(IC1-LED5)") (class "Default")
      (node (ref "BAR1") (pin "6") (pinfunction "6_6") (pintype "passive"))
      (node (ref "IC1") (pin "15") (pinfunction "LED5_15") (pintype "output"))
    )
    (net (code "77") (name "Net-(IC1-LED6)") (class "Default")
      (node (ref "BAR1") (pin "7") (pinfunction "7_7") (pintype "passive"))
      (node (ref "IC1") (pin "14") (pinfunction "LED6_14") (pintype "output"))
    )
    (net (code "78") (name "Net-(IC1-LED7)") (class "Default")
      (node (ref "BAR1") (pin "8") (pinfunction "8_8") (pintype "passive"))
      (node (ref "IC1") (pin "13") (pinfunction "LED7_13") (pintype "output"))
    )
    (net (code "79") (name "Net-(IC1-LED8)") (class "Default")
      (node (ref "BAR1") (pin "9") (pinfunction "9_9") (pintype "passive"))
      (node (ref "IC1") (pin "12") (pinfunction "LED8_12") (pintype "output"))
    )
    (net (code "80") (name "Net-(IC1-LED9)") (class "Default")
      (node (ref "BAR1") (pin "10") (pinfunction "10_10") (pintype "passive"))
      (node (ref "IC1") (pin "11") (pinfunction "LED9_11") (pintype "output"))
    )
    (net (code "81") (name "Net-(IC1-LED10)") (class "Default")
      (node (ref "BAR1") (pin "11") (pinfunction "11_11") (pintype "passive"))
      (node (ref "IC1") (pin "10") (pinfunction "LED10_10") (pintype "output"))
    )
    (net (code "82") (name "Net-(IC1-REFADJ)") (class "Default")
      (node (ref "IC1") (pin "8") (pinfunction "REFADJ_8") (pintype "passive"))
      (node (ref "R4") (pin "1") (pinfunction "1_1") (pintype "passive"))
      (node (ref "R9") (pin "2") (pinfunction "2_2") (pintype "passive"))
    )
    (net (code "83") (name "Net-(IC1-REFOUT)") (class "Default")
      (node (ref "IC1") (pin "6") (pinfunction "RHI_6") (pintype "input"))
      (node (ref "IC1") (pin "7") (pinfunction "REFOUT_7") (pintype "output"))
      (node (ref "R4") (pin "2") (pinfunction "2_2") (pintype "passive"))
    )
    (net (code "84") (name "Net-(IC1-SIGIN)") (class "Default")
      (node (ref "C1") (pin "+") (pinfunction "+_+") (pintype "passive"))
      (node (ref "IC1") (pin "5") (pinfunction "SIGIN_5") (pintype "input"))
      (node (ref "R1") (pin "1") (pinfunction "1_1") (pintype "passive"))
    )
    (net (code "85") (name "Net-(IC2-LED1)") (class "Default")
      (node (ref "BAR2") (pin "2") (pinfunction "2_2") (pintype "passive"))
      (node (ref "IC2") (pin "1") (pinfunction "LED1_1") (pintype "output"))
    )
    (net (code "86") (name "Net-(IC2-LED2)") (class "Default")
      (node (ref "BAR2") (pin "3") (pinfunction "3_3") (pintype "passive"))
      (node (ref "IC2") (pin "18") (pinfunction "LED2_18") (pintype "output"))
    )
    (net (code "87") (name "Net-(IC2-LED3)") (class "Default")
      (node (ref "BAR2") (pin "4") (pinfunction "4_4") (pintype "passive"))
      (node (ref "IC2") (pin "17") (pinfunction "LED3_17") (pintype "output"))
    )
    (net (code "88") (name "Net-(IC2-LED4)") (class "Default")
      (node (ref "BAR2") (pin "5") (pinfunction "5_5") (pintype "passive"))
      (node (ref "IC2") (pin "16") (pinfunction "LED4_16") (pintype "output"))
    )
    (net (code "89") (name "Net-(IC2-LED5)") (class "Default")
      (node (ref "BAR2") (pin "6") (pinfunction "6_6") (pintype "passive"))
      (node (ref "IC2") (pin "15") (pinfunction "LED5_15") (pintype "output"))
    )
    (net (code "90") (name "Net-(IC2-LED6)") (class "Default")
      (node (ref "BAR2") (pin "7") (pinfunction "7_7") (pintype "passive"))
      (node (ref "IC2") (pin "14") (pinfunction "LED6_14") (pintype "output"))
    )
    (net (code "91") (name "Net-(IC2-LED7)") (class "Default")
      (node (ref "BAR2") (pin "8") (pinfunction "8_8") (pintype "passive"))
      (node (ref "IC2") (pin "13") (pinfunction "LED7_13") (pintype "output"))
    )
    (net (code "92") (name "Net-(IC2-LED8)") (class "Default")
      (node (ref "BAR2") (pin "9") (pinfunction "9_9") (pintype "passive"))
      (node (ref "IC2") (pin "12") (pinfunction "LED8_12") (pintype "output"))
    )
    (net (code "93") (name "Net-(IC2-LED9)") (class "Default")
      (node (ref "BAR2") (pin "10") (pinfunction "10_10") (pintype "passive"))
      (node (ref "IC2") (pin "11") (pinfunction "LED9_11") (pintype "output"))
    )
    (net (code "94") (name "Net-(IC2-LED10)") (class "Default")
      (node (ref "BAR2") (pin "11") (pinfunction "11_11") (pintype "passive"))
      (node (ref "IC2") (pin "10") (pinfunction "LED10_10") (pintype "output"))
    )
    (net (code "95") (name "Net-(IC2-REFADJ)") (class "Default")
      (node (ref "IC2") (pin "8") (pinfunction "REFADJ_8") (pintype "passive"))
      (node (ref "R5") (pin "2") (pinfunction "2_2") (pintype "passive"))
      (node (ref "R8") (pin "2") (pinfunction "2_2") (pintype "passive"))
    )
    (net (code "96") (name "Net-(IC2-REFOUT)") (class "Default")
      (node (ref "IC2") (pin "6") (pinfunction "RHI_6") (pintype "input"))
      (node (ref "IC2") (pin "7") (pinfunction "REFOUT_7") (pintype "output"))
      (node (ref "R5") (pin "1") (pinfunction "1_1") (pintype "passive"))
    )
    (net (code "97") (name "Net-(IC2-SIGIN)") (class "Default")
      (node (ref "C2") (pin "+") (pinfunction "+_+") (pintype "passive"))
      (node (ref "IC2") (pin "5") (pinfunction "SIGIN_5") (pintype "input"))
      (node (ref "R2") (pin "1") (pinfunction "1_1") (pintype "passive"))
    )
    (net (code "98") (name "Net-(IC3-LED1)") (class "Default")
      (node (ref "BAR3") (pin "2") (pinfunction "2_2") (pintype "passive"))
      (node (ref "IC3") (pin "1") (pinfunction "LED1_1") (pintype "output"))
    )
    (net (code "99") (name "Net-(IC3-LED2)") (class "Default")
      (node (ref "BAR3") (pin "3") (pinfunction "3_3") (pintype "passive"))
      (node (ref "IC3") (pin "18") (pinfunction "LED2_18") (pintype "output"))
    )
    (net (code "100") (name "Net-(IC3-LED3)") (class "Default")
      (node (ref "BAR3") (pin "4") (pinfunction "4_4") (pintype "passive"))
      (node (ref "IC3") (pin "17") (pinfunction "LED3_17") (pintype "output"))
    )
    (net (code "101") (name "Net-(IC3-LED4)") (class "Default")
      (node (ref "BAR3") (pin "5") (pinfunction "5_5") (pintype "passive"))
      (node (ref "IC3") (pin "16") (pinfunction "LED4_16") (pintype "output"))
    )
    (net (code "102") (name "Net-(IC3-LED5)") (class "Default")
      (node (ref "BAR3") (pin "6") (pinfunction "6_6") (pintype "passive"))
      (node (ref "IC3") (pin "15") (pinfunction "LED5_15") (pintype "output"))
    )
    (net (code "103") (name "Net-(IC3-LED6)") (class "Default")
      (node (ref "BAR3") (pin "7") (pinfunction "7_7") (pintype "passive"))
      (node (ref "IC3") (pin "14") (pinfunction "LED6_14") (pintype "output"))
    )
    (net (code "104") (name "Net-(IC3-LED7)") (class "Default")
      (node (ref "BAR3") (pin "8") (pinfunction "8_8") (pintype "passive"))
      (node (ref "IC3") (pin "13") (pinfunction "LED7_13") (pintype "output"))
    )
    (net (code "105") (name "Net-(IC3-LED8)") (class "Default")
      (node (ref "BAR3") (pin "9") (pinfunction "9_9") (pintype "passive"))
      (node (ref "IC3") (pin "12") (pinfunction "LED8_12") (pintype "output"))
    )
    (net (code "106") (name "Net-(IC3-LED9)") (class "Default")
      (node (ref "BAR3") (pin "10") (pinfunction "10_10") (pintype "passive"))
      (node (ref "IC3") (pin "11") (pinfunction "LED9_11") (pintype "output"))
    )
    (net (code "107") (name "Net-(IC3-LED10)") (class "Default")
      (node (ref "BAR3") (pin "11") (pinfunction "11_11") (pintype "passive"))
      (node (ref "IC3") (pin "10") (pinfunction "LED10_10") (pintype "output"))
    )
    (net (code "108") (name "Net-(IC3-REFADJ)") (class "Default")
      (node (ref "IC3") (pin "8") (pinfunction "REFADJ_8") (pintype "passive"))
      (node (ref "R6") (pin "2") (pinfunction "2_2") (pintype "passive"))
      (node (ref "R7") (pin "2") (pinfunction "2_2") (pintype "passive"))
    )
    (net (code "109") (name "Net-(IC3-REFOUT)") (class "Default")
      (node (ref "IC3") (pin "6") (pinfunction "RHI_6") (pintype "input"))
      (node (ref "IC3") (pin "7") (pinfunction "REFOUT_7") (pintype "output"))
      (node (ref "R6") (pin "1") (pinfunction "1_1") (pintype "passive"))
    )
    (net (code "110") (name "Net-(IC3-SIGIN)") (class "Default")
      (node (ref "C3") (pin "+") (pinfunction "+_+") (pintype "passive"))
      (node (ref "IC3") (pin "5") (pinfunction "SIGIN_5") (pintype "input"))
      (node (ref "R3") (pin "1") (pinfunction "1_1") (pintype "passive"))
    )
    (net (code "111") (name "Net-(IC4-PB6(XTAL1{slash}TOSC1{slash}PCINT6))") (class "Default")
      (node (ref "C4") (pin "1") (pinfunction "1_1") (pintype "passive"))
      (node (ref "IC4") (pin "9") (pinfunction "PB6(XTAL1/TOSC1/PCINT6)_9") (pintype "bidirectional"))
      (node (ref "Q1") (pin "1") (pinfunction "1_1") (pintype "passive"))
    )
    (net (code "112") (name "Net-(IC4-PB7(XTAL2{slash}TOSC2{slash}PCINT7))") (class "Default")
      (node (ref "C5") (pin "1") (pinfunction "1_1") (pintype "passive"))
      (node (ref "IC4") (pin "10") (pinfunction "PB7(XTAL2/TOSC2/PCINT7)_10") (pintype "bidirectional"))
      (node (ref "Q1") (pin "2") (pinfunction "2_2") (pintype "passive"))
    )
    (net (code "113") (name "Net-(IC5A-QA)") (class "Default")
      (node (ref "IC5") (pin "15") (pinfunction "QA_15") (pintype "tri_state"))
      (node (ref "R39") (pin "1") (pinfunction "1_1") (pintype "passive"))
    )
    (net (code "114") (name "Net-(IC5A-QB)") (class "Default")
      (node (ref "IC5") (pin "1") (pinfunction "QB_1") (pintype "tri_state"))
      (node (ref "R40") (pin "1") (pinfunction "1_1") (pintype "passive"))
    )
    (net (code "115") (name "Net-(IC5A-QC)") (class "Default")
      (node (ref "IC5") (pin "2") (pinfunction "QC_2") (pintype "tri_state"))
      (node (ref "R41") (pin "1") (pinfunction "1_1") (pintype "passive"))
    )
    (net (code "116") (name "Net-(IC5A-QD)") (class "Default")
      (node (ref "IC5") (pin "3") (pinfunction "QD_3") (pintype "tri_state"))
      (node (ref "R42") (pin "1") (pinfunction "1_1") (pintype "passive"))
    )
    (net (code "117") (name "Net-(IC5A-QE)") (class "Default")
      (node (ref "IC5") (pin "4") (pinfunction "QE_4") (pintype "tri_state"))
      (node (ref "R43") (pin "1") (pinfunction "1_1") (pintype "passive"))
    )
    (net (code "118") (name "Net-(IC5A-QF)") (class "Default")
      (node (ref "IC5") (pin "5") (pinfunction "QF_5") (pintype "tri_state"))
      (node (ref "R44") (pin "1") (pinfunction "1_1") (pintype "passive"))
    )
    (net (code "119") (name "Net-(IC5A-QG)") (class "Default")
      (node (ref "IC5") (pin "6") (pinfunction "QG_6") (pintype "tri_state"))
      (node (ref "R45") (pin "1") (pinfunction "1_1") (pintype "passive"))
    )
    (net (code "120") (name "Net-(IC5A-QH)") (class "Default")
      (node (ref "IC5") (pin "7") (pinfunction "QH_7") (pintype "tri_state"))
      (node (ref "R46") (pin "1") (pinfunction "1_1") (pintype "passive"))
    )
    (net (code "121") (name "Net-(IC6A-QA)") (class "Default")
      (node (ref "IC6") (pin "15") (pinfunction "QA_15") (pintype "tri_state"))
      (node (ref "R55") (pin "1") (pinfunction "1_1") (pintype "passive"))
    )
    (net (code "122") (name "Net-(IC6A-QB)") (class "Default")
      (node (ref "IC6") (pin "1") (pinfunction "QB_1") (pintype "tri_state"))
      (node (ref "R56") (pin "1") (pinfunction "1_1") (pintype "passive"))
    )
    (net (code "123") (name "Net-(IC6A-QC)") (class "Default")
      (node (ref "IC6") (pin "2") (pinfunction "QC_2") (pintype "tri_state"))
      (node (ref "R57") (pin "1") (pinfunction "1_1") (pintype "passive"))
    )
    (net (code "124") (name "Net-(IC6A-QD)") (class "Default")
      (node (ref "IC6") (pin "3") (pinfunction "QD_3") (pintype "tri_state"))
      (node (ref "R58") (pin "1") (pinfunction "1_1") (pintype "passive"))
    )
    (net (code "125") (name "Net-(IC6A-QE)") (class "Default")
      (node (ref "IC6") (pin "4") (pinfunction "QE_4") (pintype "tri_state"))
      (node (ref "R59") (pin "1") (pinfunction "1_1") (pintype "passive"))
    )
    (net (code "126") (name "Net-(IC6A-QF)") (class "Default")
      (node (ref "IC6") (pin "5") (pinfunction "QF_5") (pintype "tri_state"))
      (node (ref "R60") (pin "1") (pinfunction "1_1") (pintype "passive"))
    )
    (net (code "127") (name "Net-(IC6A-QG)") (class "Default")
      (node (ref "IC6") (pin "6") (pinfunction "QG_6") (pintype "tri_state"))
      (node (ref "R61") (pin "1") (pinfunction "1_1") (pintype "passive"))
    )
    (net (code "128") (name "Net-(IC6A-QH)") (class "Default")
      (node (ref "IC6") (pin "7") (pinfunction "QH_7") (pintype "tri_state"))
      (node (ref "R62") (pin "1") (pinfunction "1_1") (pintype "passive"))
    )
    (net (code "129") (name "Net-(IC6A-QH*)") (class "Default")
      (node (ref "IC6") (pin "9") (pinfunction "QH*_9") (pintype "tri_state"))
      (node (ref "IC7") (pin "14") (pinfunction "SER_14") (pintype "input"))
    )
    (net (code "130") (name "Net-(IC7A-QA)") (class "Default")
      (node (ref "IC7") (pin "15") (pinfunction "QA_15") (pintype "tri_state"))
      (node (ref "IC9") (pin "7") (pinfunction "IA_7") (pintype "input"))
    )
    (net (code "131") (name "Net-(IC7A-QB)") (class "Default")
      (node (ref "IC7") (pin "1") (pinfunction "QB_1") (pintype "tri_state"))
      (node (ref "IC9") (pin "1") (pinfunction "IB_1") (pintype "input"))
    )
    (net (code "132") (name "Net-(IC7A-QC)") (class "Default")
      (node (ref "IC7") (pin "2") (pinfunction "QC_2") (pintype "tri_state"))
      (node (ref "IC9") (pin "2") (pinfunction "IC_2") (pintype "input"))
    )
    (net (code "133") (name "Net-(IC7A-QD)") (class "Default")
      (node (ref "IC7") (pin "3") (pinfunction "QD_3") (pintype "tri_state"))
      (node (ref "IC9") (pin "6") (pinfunction "ID_6") (pintype "input"))
    )
    (net (code "134") (name "Net-(IC7A-QH*)") (class "Default")
      (node (ref "IC7") (pin "9") (pinfunction "QH*_9") (pintype "tri_state"))
      (node (ref "IC8") (pin "14") (pinfunction "SER_14") (pintype "input"))
    )
    (net (code "135") (name "Net-(IC9A-A)") (class "Default")
      (node (ref "IC9") (pin "13") (pinfunction "A_13") (pintype "output"))
      (node (ref "R11") (pin "1") (pinfunction "1_1") (pintype "passive"))
    )
    (net (code "136") (name "Net-(IC9A-B)") (class "Default")
      (node (ref "IC9") (pin "12") (pinfunction "B_12") (pintype "output"))
      (node (ref "R12") (pin "1") (pinfunction "1_1") (pintype "passive"))
    )
    (net (code "137") (name "Net-(IC9A-C)") (class "Default")
      (node (ref "IC9") (pin "11") (pinfunction "C_11") (pintype "output"))
      (node (ref "R13") (pin "1") (pinfunction "1_1") (pintype "passive"))
    )
    (net (code "138") (name "Net-(IC9A-D)") (class "Default")
      (node (ref "IC9") (pin "10") (pinfunction "D_10") (pintype "output"))
      (node (ref "R14") (pin "1") (pinfunction "1_1") (pintype "passive"))
    )
    (net (code "139") (name "Net-(IC9A-E)") (class "Default")
      (node (ref "IC9") (pin "9") (pinfunction "E_9") (pintype "output"))
      (node (ref "R15") (pin "1") (pinfunction "1_1") (pintype "passive"))
    )
    (net (code "140") (name "Net-(IC9A-F)") (class "Default")
      (node (ref "IC9") (pin "15") (pinfunction "F_15") (pintype "output"))
      (node (ref "R16") (pin "1") (pinfunction "1_1") (pintype "passive"))
    )
    (net (code "141") (name "Net-(IC9A-G)") (class "Default")
      (node (ref "IC9") (pin "14") (pinfunction "G_14") (pintype "output"))
      (node (ref "R17") (pin "1") (pinfunction "1_1") (pintype "passive"))
    )
    (net (code "142") (name "Net-(IC10A-A)") (class "Default")
      (node (ref "IC10") (pin "13") (pinfunction "A_13") (pintype "output"))
      (node (ref "R18") (pin "1") (pinfunction "1_1") (pintype "passive"))
    )
    (net (code "143") (name "Net-(IC10A-B)") (class "Default")
      (node (ref "IC10") (pin "12") (pinfunction "B_12") (pintype "output"))
      (node (ref "R19") (pin "1") (pinfunction "1_1") (pintype "passive"))
    )
    (net (code "144") (name "Net-(IC10A-C)") (class "Default")
      (node (ref "IC10") (pin "11") (pinfunction "C_11") (pintype "output"))
      (node (ref "R20") (pin "1") (pinfunction "1_1") (pintype "passive"))
    )
    (net (code "145") (name "Net-(IC10A-D)") (class "Default")
      (node (ref "IC10") (pin "10") (pinfunction "D_10") (pintype "output"))
      (node (ref "R21") (pin "1") (pinfunction "1_1") (pintype "passive"))
    )
    (net (code "146") (name "Net-(IC10A-E)") (class "Default")
      (node (ref "IC10") (pin "9") (pinfunction "E_9") (pintype "output"))
      (node (ref "R22") (pin "1") (pinfunction "1_1") (pintype "passive"))
    )
    (net (code "147") (name "Net-(IC10A-F)") (class "Default")
      (node (ref "IC10") (pin "15") (pinfunction "F_15") (pintype "output"))
      (node (ref "R23") (pin "1") (pinfunction "1_1") (pintype "passive"))
    )
    (net (code "148") (name "Net-(IC10A-G)") (class "Default")
      (node (ref "IC10") (pin "14") (pinfunction "G_14") (pintype "output"))
      (node (ref "R24") (pin "1") (pinfunction "1_1") (pintype "passive"))
    )
    (net (code "149") (name "Net-(IC10A-IA)") (class "Default")
      (node (ref "IC10") (pin "7") (pinfunction "IA_7") (pintype "input"))
      (node (ref "IC7") (pin "4") (pinfunction "QE_4") (pintype "tri_state"))
    )
    (net (code "150") (name "Net-(IC10A-IB)") (class "Default")
      (node (ref "IC10") (pin "1") (pinfunction "IB_1") (pintype "input"))
      (node (ref "IC7") (pin "5") (pinfunction "QF_5") (pintype "tri_state"))
    )
    (net (code "151") (name "Net-(IC10A-IC)") (class "Default")
      (node (ref "IC10") (pin "2") (pinfunction "IC_2") (pintype "input"))
      (node (ref "IC7") (pin "6") (pinfunction "QG_6") (pintype "tri_state"))
    )
    (net (code "152") (name "Net-(IC10A-ID)") (class "Default")
      (node (ref "IC10") (pin "6") (pinfunction "ID_6") (pintype "input"))
      (node (ref "IC7") (pin "7") (pinfunction "QH_7") (pintype "tri_state"))
    )
    (net (code "153") (name "Net-(IC11A-A)") (class "Default")
      (node (ref "IC11") (pin "13") (pinfunction "A_13") (pintype "output"))
      (node (ref "R25") (pin "1") (pinfunction "1_1") (pintype "passive"))
    )
    (net (code "154") (name "Net-(IC11A-B)") (class "Default")
      (node (ref "IC11") (pin "12") (pinfunction "B_12") (pintype "output"))
      (node (ref "R26") (pin "1") (pinfunction "1_1") (pintype "passive"))
    )
    (net (code "155") (name "Net-(IC11A-C)") (class "Default")
      (node (ref "IC11") (pin "11") (pinfunction "C_11") (pintype "output"))
      (node (ref "R27") (pin "1") (pinfunction "1_1") (pintype "passive"))
    )
    (net (code "156") (name "Net-(IC11A-D)") (class "Default")
      (node (ref "IC11") (pin "10") (pinfunction "D_10") (pintype "output"))
      (node (ref "R28") (pin "1") (pinfunction "1_1") (pintype "passive"))
    )
    (net (code "157") (name "Net-(IC11A-E)") (class "Default")
      (node (ref "IC11") (pin "9") (pinfunction "E_9") (pintype "output"))
      (node (ref "R29") (pin "1") (pinfunction "1_1") (pintype "passive"))
    )
    (net (code "158") (name "Net-(IC11A-F)") (class "Default")
      (node (ref "IC11") (pin "15") (pinfunction "F_15") (pintype "output"))
      (node (ref "R30") (pin "1") (pinfunction "1_1") (pintype "passive"))
    )
    (net (code "159") (name "Net-(IC11A-G)") (class "Default")
      (node (ref "IC11") (pin "14") (pinfunction "G_14") (pintype "output"))
      (node (ref "R31") (pin "1") (pinfunction "1_1") (pintype "passive"))
    )
    (net (code "160") (name "Net-(IC11A-IA)") (class "Default")
      (node (ref "IC11") (pin "7") (pinfunction "IA_7") (pintype "input"))
      (node (ref "IC8") (pin "15") (pinfunction "QA_15") (pintype "tri_state"))
    )
    (net (code "161") (name "Net-(IC11A-IB)") (class "Default")
      (node (ref "IC11") (pin "1") (pinfunction "IB_1") (pintype "input"))
      (node (ref "IC8") (pin "1") (pinfunction "QB_1") (pintype "tri_state"))
    )
    (net (code "162") (name "Net-(IC11A-IC)") (class "Default")
      (node (ref "IC11") (pin "2") (pinfunction "IC_2") (pintype "input"))
      (node (ref "IC8") (pin "2") (pinfunction "QC_2") (pintype "tri_state"))
    )
    (net (code "163") (name "Net-(IC11A-ID)") (class "Default")
      (node (ref "IC11") (pin "6") (pinfunction "ID_6") (pintype "input"))
      (node (ref "IC8") (pin "3") (pinfunction "QD_3") (pintype "tri_state"))
    )
    (net (code "164") (name "Net-(IC12A-A)") (class "Default")
      (node (ref "IC12") (pin "13") (pinfunction "A_13") (pintype "output"))
      (node (ref "R32") (pin "1") (pinfunction "1_1") (pintype "passive"))
    )
    (net (code "165") (name "Net-(IC12A-B)") (class "Default")
      (node (ref "IC12") (pin "12") (pinfunction "B_12") (pintype "output"))
      (node (ref "R33") (pin "1") (pinfunction "1_1") (pintype "passive"))
    )
    (net (code "166") (name "Net-(IC12A-C)") (class "Default")
      (node (ref "IC12") (pin "11") (pinfunction "C_11") (pintype "output"))
      (node (ref "R34") (pin "1") (pinfunction "1_1") (pintype "passive"))
    )
    (net (code "167") (name "Net-(IC12A-D)") (class "Default")
      (node (ref "IC12") (pin "10") (pinfunction "D_10") (pintype "output"))
      (node (ref "R35") (pin "1") (pinfunction "1_1") (pintype "passive"))
    )
    (net (code "168") (name "Net-(IC12A-E)") (class "Default")
      (node (ref "IC12") (pin "9") (pinfunction "E_9") (pintype "output"))
      (node (ref "R36") (pin "1") (pinfunction "1_1") (pintype "passive"))
    )
    (net (code "169") (name "Net-(IC12A-F)") (class "Default")
      (node (ref "IC12") (pin "15") (pinfunction "F_15") (pintype "output"))
      (node (ref "R37") (pin "1") (pinfunction "1_1") (pintype "passive"))
    )
    (net (code "170") (name "Net-(IC12A-G)") (class "Default")
      (node (ref "IC12") (pin "14") (pinfunction "G_14") (pintype "output"))
      (node (ref "R38") (pin "1") (pinfunction "1_1") (pintype "passive"))
    )
    (net (code "171") (name "Net-(IC12A-IA)") (class "Default")
      (node (ref "IC12") (pin "7") (pinfunction "IA_7") (pintype "input"))
      (node (ref "IC8") (pin "4") (pinfunction "QE_4") (pintype "tri_state"))
    )
    (net (code "172") (name "Net-(IC12A-IB)") (class "Default")
      (node (ref "IC12") (pin "1") (pinfunction "IB_1") (pintype "input"))
      (node (ref "IC8") (pin "5") (pinfunction "QF_5") (pintype "tri_state"))
    )
    (net (code "173") (name "Net-(IC12A-IC)") (class "Default")
      (node (ref "IC12") (pin "2") (pinfunction "IC_2") (pintype "input"))
      (node (ref "IC8") (pin "6") (pinfunction "QG_6") (pintype "tri_state"))
    )
    (net (code "174") (name "Net-(IC12A-ID)") (class "Default")
      (node (ref "IC12") (pin "6") (pinfunction "ID_6") (pintype "input"))
      (node (ref "IC8") (pin "7") (pinfunction "QH_7") (pintype "tri_state"))
    )
    (net (code "175") (name "Net-(IC14A-QA)") (class "Default")
      (node (ref "IC14") (pin "15") (pinfunction "QA_15") (pintype "tri_state"))
      (node (ref "R47") (pin "1") (pinfunction "1_1") (pintype "passive"))
    )
    (net (code "176") (name "Net-(IC14A-QB)") (class "Default")
      (node (ref "IC14") (pin "1") (pinfunction "QB_1") (pintype "tri_state"))
      (node (ref "R48") (pin "1") (pinfunction "1_1") (pintype "passive"))
    )
    (net (code "177") (name "Net-(IC14A-QC)") (class "Default")
      (node (ref "IC14") (pin "2") (pinfunction "QC_2") (pintype "tri_state"))
      (node (ref "R49") (pin "1") (pinfunction "1_1") (pintype "passive"))
    )
    (net (code "178") (name "Net-(IC14A-QD)") (class "Default")
      (node (ref "IC14") (pin "3") (pinfunction "QD_3") (pintype "tri_state"))
      (node (ref "R50") (pin "1") (pinfunction "1_1") (pintype "passive"))
    )
    (net (code "179") (name "Net-(IC14A-QE)") (class "Default")
      (node (ref "IC14") (pin "4") (pinfunction "QE_4") (pintype "tri_state"))
      (node (ref "R51") (pin "1") (pinfunction "1_1") (pintype "passive"))
    )
    (net (code "180") (name "Net-(IC14A-QF)") (class "Default")
      (node (ref "IC14") (pin "5") (pinfunction "QF_5") (pintype "tri_state"))
      (node (ref "R52") (pin "1") (pinfunction "1_1") (pintype "passive"))
    )
    (net (code "181") (name "Net-(IC14A-QG)") (class "Default")
      (node (ref "IC14") (pin "6") (pinfunction "QG_6") (pintype "tri_state"))
      (node (ref "R53") (pin "1") (pinfunction "1_1") (pintype "passive"))
    )
    (net (code "182") (name "Net-(IC14A-QH)") (class "Default")
      (node (ref "IC14") (pin "7") (pinfunction "QH_7") (pintype "tri_state"))
      (node (ref "R54") (pin "1") (pinfunction "1_1") (pintype "passive"))
    )
    (net (code "183") (name "Net-(IC14A-QH*)") (class "Default")
      (node (ref "IC14") (pin "9") (pinfunction "QH*_9") (pintype "tri_state"))
      (node (ref "IC6") (pin "14") (pinfunction "SER_14") (pintype "input"))
    )
    (net (code "184") (name "Net-(IC14A-SER)") (class "Default")
      (node (ref "IC14") (pin "14") (pinfunction "SER_14") (pintype "input"))
      (node (ref "IC5") (pin "9") (pinfunction "QH*_9") (pintype "tri_state"))
    )
    (net (code "185") (name "Net-(IC15A-QA)") (class "Default")
      (node (ref "IC15") (pin "15") (pinfunction "QA_15") (pintype "tri_state"))
      (node (ref "R73") (pin "1") (pinfunction "1_1") (pintype "passive"))
    )
    (net (code "186") (name "Net-(IC15A-QB)") (class "Default")
      (node (ref "IC15") (pin "1") (pinfunction "QB_1") (pintype "tri_state"))
      (node (ref "R74") (pin "1") (pinfunction "1_1") (pintype "passive"))
    )
    (net (code "187") (name "Net-(IC15A-QC)") (class "Default")
      (node (ref "IC15") (pin "2") (pinfunction "QC_2") (pintype "tri_state"))
      (node (ref "R75") (pin "1") (pinfunction "1_1") (pintype "passive"))
    )
    (net (code "188") (name "Net-(IC15A-QD)") (class "Default")
      (node (ref "IC15") (pin "3") (pinfunction "QD_3") (pintype "tri_state"))
      (node (ref "R76") (pin "1") (pinfunction "1_1") (pintype "passive"))
    )
    (net (code "189") (name "Net-(IC15A-QE)") (class "Default")
      (node (ref "IC15") (pin "4") (pinfunction "QE_4") (pintype "tri_state"))
      (node (ref "R77") (pin "1") (pinfunction "1_1") (pintype "passive"))
    )
    (net (code "190") (name "Net-(IC15A-QF)") (class "Default")
      (node (ref "IC15") (pin "5") (pinfunction "QF_5") (pintype "tri_state"))
      (node (ref "R78") (pin "1") (pinfunction "1_1") (pintype "passive"))
    )
    (net (code "191") (name "Net-(IC15A-QG)") (class "Default")
      (node (ref "IC15") (pin "6") (pinfunction "QG_6") (pintype "tri_state"))
      (node (ref "R79") (pin "1") (pinfunction "1_1") (pintype "passive"))
    )
    (net (code "192") (name "Net-(IC15A-QH)") (class "Default")
      (node (ref "IC15") (pin "7") (pinfunction "QH_7") (pintype "tri_state"))
      (node (ref "R80") (pin "1") (pinfunction "1_1") (pintype "passive"))
    )
    (net (code "193") (name "Net-(IC15A-QH*)") (class "Default")
      (node (ref "IC15") (pin "9") (pinfunction "QH*_9") (pintype "tri_state"))
      (node (ref "IC5") (pin "14") (pinfunction "SER_14") (pintype "input"))
    )
    (net (code "194") (name "Net-(JP2-Pad1)") (class "Default")
      (node (ref "JP2") (pin "1") (pinfunction "1_1") (pintype "passive"))
      (node (ref "JP2") (pin "11") (pinfunction "11_11") (pintype "passive"))
      (node (ref "JP2") (pin "13") (pinfunction "13_13") (pintype "passive"))
      (node (ref "JP2") (pin "3") (pinfunction "3_3") (pintype "passive"))
      (node (ref "JP2") (pin "5") (pinfunction "5_5") (pintype "passive"))
      (node (ref "JP2") (pin "7") (pinfunction "7_7") (pintype "passive"))
      (node (ref "JP2") (pin "9") (pinfunction "9_9") (pintype "passive"))
      (node (ref "R70") (pin "1") (pinfunction "1_1") (pintype "passive"))
      (node (ref "R71") (pin "2") (pinfunction "2_2") (pintype "passive"))
    )
    (net (code "195") (name "Net-(LGT1-Pad1)") (class "Default")
      (node (ref "LGT1") (pin "1") (pinfunction "1_1") (pintype "passive"))
      (node (ref "R39") (pin "2") (pinfunction "2_2") (pintype "passive"))
    )
    (net (code "196") (name "Net-(LGT1-Pad2)") (class "Default")
      (node (ref "LGT1") (pin "2") (pinfunction "2_2") (pintype "passive"))
      (node (ref "R40") (pin "2") (pinfunction "2_2") (pintype "passive"))
    )
    (net (code "197") (name "Net-(LGT1-Pad3)") (class "Default")
      (node (ref "LGT1") (pin "3") (pinfunction "3_3") (pintype "passive"))
      (node (ref "R41") (pin "2") (pinfunction "2_2") (pintype "passive"))
    )
    (net (code "198") (name "Net-(LGT1-Pad4)") (class "Default")
      (node (ref "LGT1") (pin "4") (pinfunction "4_4") (pintype "passive"))
      (node (ref "R42") (pin "2") (pinfunction "2_2") (pintype "passive"))
    )
    (net (code "199") (name "Net-(LGT1-Pad5)") (class "Default")
      (node (ref "LGT1") (pin "5") (pinfunction "5_5") (pintype "passive"))
      (node (ref "R43") (pin "2") (pinfunction "2_2") (pintype "passive"))
    )
    (net (code "200") (name "Net-(LGT1-Pad6)") (class "Default")
      (node (ref "LGT1") (pin "6") (pinfunction "6_6") (pintype "passive"))
      (node (ref "R44") (pin "2") (pinfunction "2_2") (pintype "passive"))
    )
    (net (code "201") (name "Net-(LGT1-Pad7)") (class "Default")
      (node (ref "LGT1") (pin "7") (pinfunction "7_7") (pintype "passive"))
      (node (ref "R45") (pin "2") (pinfunction "2_2") (pintype "passive"))
    )
    (net (code "202") (name "Net-(LGT1-Pad8)") (class "Default")
      (node (ref "LGT1") (pin "8") (pinfunction "8_8") (pintype "passive"))
      (node (ref "R46") (pin "2") (pinfunction "2_2") (pintype "passive"))
    )
    (net (code "203") (name "Net-(LGT2-Pad1)") (class "Default")
      (node (ref "LGT2") (pin "1") (pinfunction "1_1") (pintype "passive"))
      (node (ref "R47") (pin "2") (pinfunction "2_2") (pintype "passive"))
    )
    (net (code "204") (name "Net-(LGT2-Pad2)") (class "Default")
      (node (ref "LGT2") (pin "2") (pinfunction "2_2") (pintype "passive"))
      (node (ref "R48") (pin "2") (pinfunction "2_2") (pintype "passive"))
    )
    (net (code "205") (name "Net-(LGT2-Pad3)") (class "Default")
      (node (ref "LGT2") (pin "3") (pinfunction "3_3") (pintype "passive"))
      (node (ref "R49") (pin "2") (pinfunction "2_2") (pintype "passive"))
    )
    (net (code "206") (name "Net-(LGT2-Pad4)") (class "Default")
      (node (ref "LGT2") (pin "4") (pinfunction "4_4") (pintype "passive"))
      (node (ref "R50") (pin "2") (pinfunction "2_2") (pintype "passive"))
    )
    (net (code "207") (name "Net-(LGT2-Pad5)") (class "Default")
      (node (ref "LGT2") (pin "5") (pinfunction "5_5") (pintype "passive"))
      (node (ref "R51") (pin "2") (pinfunction "2_2") (pintype "passive"))
    )
    (net (code "208") (name "Net-(LGT2-Pad6)") (class "Default")
      (node (ref "LGT2") (pin "6") (pinfunction "6_6") (pintype "passive"))
      (node (ref "R52") (pin "2") (pinfunction "2_2") (pintype "passive"))
    )
    (net (code "209") (name "Net-(LGT2-Pad7)") (class "Default")
      (node (ref "LGT2") (pin "7") (pinfunction "7_7") (pintype "passive"))
      (node (ref "R53") (pin "2") (pinfunction "2_2") (pintype "passive"))
    )
    (net (code "210") (name "Net-(LGT2-Pad8)") (class "Default")
      (node (ref "LGT2") (pin "8") (pinfunction "8_8") (pintype "passive"))
      (node (ref "R54") (pin "2") (pinfunction "2_2") (pintype "passive"))
    )
    (net (code "211") (name "Net-(LGT3-Pad1)") (class "Default")
      (node (ref "LGT3") (pin "1") (pinfunction "1_1") (pintype "passive"))
      (node (ref "R55") (pin "2") (pinfunction "2_2") (pintype "passive"))
    )
    (net (code "212") (name "Net-(LGT3-Pad2)") (class "Default")
      (node (ref "LGT3") (pin "2") (pinfunction "2_2") (pintype "passive"))
      (node (ref "R56") (pin "2") (pinfunction "2_2") (pintype "passive"))
    )
    (net (code "213") (name "Net-(LGT3-Pad3)") (class "Default")
      (node (ref "LGT3") (pin "3") (pinfunction "3_3") (pintype "passive"))
      (node (ref "R57") (pin "2") (pinfunction "2_2") (pintype "passive"))
    )
    (net (code "214") (name "Net-(LGT3-Pad4)") (class "Default")
      (node (ref "LGT3") (pin "4") (pinfunction "4_4") (pintype "passive"))
      (node (ref "R58") (pin "2") (pinfunction "2_2") (pintype "passive"))
    )
    (net (code "215") (name "Net-(LGT3-Pad5)") (class "Default")
      (node (ref "LGT3") (pin "5") (pinfunction "5_5") (pintype "passive"))
      (node (ref "R59") (pin "2") (pinfunction "2_2") (pintype "passive"))
    )
    (net (code "216") (name "Net-(LGT3-Pad6)") (class "Default")
      (node (ref "LGT3") (pin "6") (pinfunction "6_6") (pintype "passive"))
      (node (ref "R60") (pin "2") (pinfunction "2_2") (pintype "passive"))
    )
    (net (code "217") (name "Net-(LGT3-Pad7)") (class "Default")
      (node (ref "LGT3") (pin "7") (pinfunction "7_7") (pintype "passive"))
      (node (ref "R61") (pin "2") (pinfunction "2_2") (pintype "passive"))
    )
    (net (code "218") (name "Net-(LGT3-Pad8)") (class "Default")
      (node (ref "LGT3") (pin "8") (pinfunction "8_8") (pintype "passive"))
      (node (ref "R62") (pin "2") (pinfunction "2_2") (pintype "passive"))
    )
    (net (code "219") (name "Net-(LGT4-Pad1)") (class "Default")
      (node (ref "LGT4") (pin "1") (pinfunction "1_1") (pintype "passive"))
      (node (ref "R73") (pin "2") (pinfunction "2_2") (pintype "passive"))
    )
    (net (code "220") (name "Net-(LGT4-Pad2)") (class "Default")
      (node (ref "LGT4") (pin "2") (pinfunction "2_2") (pintype "passive"))
      (node (ref "R74") (pin "2") (pinfunction "2_2") (pintype "passive"))
    )
    (net (code "221") (name "Net-(LGT4-Pad3)") (class "Default")
      (node (ref "LGT4") (pin "3") (pinfunction "3_3") (pintype "passive"))
      (node (ref "R75") (pin "2") (pinfunction "2_2") (pintype "passive"))
    )
    (net (code "222") (name "Net-(LGT4-Pad4)") (class "Default")
      (node (ref "LGT4") (pin "4") (pinfunction "4_4") (pintype "passive"))
      (node (ref "R76") (pin "2") (pinfunction "2_2") (pintype "passive"))
    )
    (net (code "223") (name "Net-(LGT4-Pad5)") (class "Default")
      (node (ref "LGT4") (pin "5") (pinfunction "5_5") (pintype "passive"))
      (node (ref "R77") (pin "2") (pinfunction "2_2") (pintype "passive"))
    )
    (net (code "224") (name "Net-(LGT4-Pad6)") (class "Default")
      (node (ref "LGT4") (pin "6") (pinfunction "6_6") (pintype "passive"))
      (node (ref "R78") (pin "2") (pinfunction "2_2") (pintype "passive"))
    )
    (net (code "225") (name "Net-(LGT4-Pad7)") (class "Default")
      (node (ref "LGT4") (pin "7") (pinfunction "7_7") (pintype "passive"))
      (node (ref "R79") (pin "2") (pinfunction "2_2") (pintype "passive"))
    )
    (net (code "226") (name "Net-(LGT4-Pad8)") (class "Default")
      (node (ref "LGT4") (pin "8") (pinfunction "8_8") (pintype "passive"))
      (node (ref "R80") (pin "2") (pinfunction "2_2") (pintype "passive"))
    )
    (net (code "227") (name "VCC") (class "Default")
      (node (ref "BAR1") (pin "1") (pinfunction "1_1") (pintype "passive"))
      (node (ref "BAR2") (pin "1") (pinfunction "1_1") (pintype "passive"))
      (node (ref "BAR3") (pin "1") (pinfunction "1_1") (pintype "passive"))
      (node (ref "C6") (pin "1") (pinfunction "1_1") (pintype "passive"))
      (node (ref "IC1") (pin "3") (pinfunction "V+_3") (pintype "power_in"))
      (node (ref "IC1") (pin "9") (pinfunction "MODE_9") (pintype "input"))
      (node (ref "IC10") (pin "16") (pinfunction "VCC_16") (pintype "power_in"))
      (node (ref "IC10") (pin "3") (pinfunction "LT_3") (pintype "input"))
      (node (ref "IC10") (pin "5") (pinfunction "RBI_5") (pintype "input"))
      (node (ref "IC11") (pin "16") (pinfunction "VCC_16") (pintype "power_in"))
      (node (ref "IC11") (pin "3") (pinfunction "LT_3") (pintype "input"))
      (node (ref "IC11") (pin "5") (pinfunction "RBI_5") (pintype "input"))
      (node (ref "IC12") (pin "16") (pinfunction "VCC_16") (pintype "power_in"))
      (node (ref "IC12") (pin "3") (pinfunction "LT_3") (pintype "input"))
      (node (ref "IC12") (pin "5") (pinfunction "RBI_5") (pintype "input"))
      (node (ref "IC13") (pin "16") (pinfunction "VDD_16") (pintype "power_in"))
      (node (ref "IC14") (pin "16") (pinfunction "VCC_16") (pintype "power_in"))
      (node (ref "IC2") (pin "3") (pinfunction "V+_3") (pintype "power_in"))
      (node (ref "IC2") (pin "9") (pinfunction "MODE_9") (pintype "input"))
      (node (ref "IC3") (pin "3") (pinfunction "V+_3") (pintype "power_in"))
      (node (ref "IC3") (pin "9") (pinfunction "MODE_9") (pintype "input"))
      (node (ref "IC4") (pin "20") (pinfunction "AVCC_20") (pintype "passive"))
      (node (ref "IC4") (pin "21") (pinfunction "AREF_21") (pintype "passive"))
      (node (ref "IC4") (pin "7") (pinfunction "VCC_7") (pintype "power_in"))
      (node (ref "IC5") (pin "16") (pinfunction "VCC_16") (pintype "power_in"))
      (node (ref "IC6") (pin "16") (pinfunction "VCC_16") (pintype "power_in"))
      (node (ref "IC7") (pin "16") (pinfunction "VCC_16") (pintype "power_in"))
      (node (ref "IC8") (pin "16") (pinfunction "VCC_16") (pintype "power_in"))
      (node (ref "IC9") (pin "16") (pinfunction "VCC_16") (pintype "power_in"))
      (node (ref "IC9") (pin "3") (pinfunction "LT_3") (pintype "input"))
      (node (ref "IC9") (pin "5") (pinfunction "RBI_5") (pintype "input"))
      (node (ref "ISP") (pin "2") (pinfunction "2_2") (pintype "passive"))
      (node (ref "Q10") (pin "3") (pinfunction "C_3") (pintype "passive"))
      (node (ref "Q11") (pin "3") (pinfunction "C_3") (pintype "passive"))
      (node (ref "Q2") (pin "3") (pinfunction "C_3") (pintype "passive"))
      (node (ref "Q3") (pin "3") (pinfunction "C_3") (pintype "passive"))
      (node (ref "Q4") (pin "3") (pinfunction "C_3") (pintype "passive"))
      (node (ref "Q5") (pin "3") (pinfunction "C_3") (pintype "passive"))
      (node (ref "Q6") (pin "3") (pinfunction "C_3") (pintype "passive"))
      (node (ref "Q7") (pin "3") (pinfunction "C_3") (pintype "passive"))
      (node (ref "Q8") (pin "3") (pinfunction "C_3") (pintype "passive"))
      (node (ref "Q9") (pin "3") (pinfunction "C_3") (pintype "passive"))
      (node (ref "R10") (pin "2") (pinfunction "2_2") (pintype "passive"))
      (node (ref "R63") (pin "2") (pinfunction "2_2") (pintype "passive"))
    )
    (net (code "228") (name "unconnected-(IC4-PB0(ICP1{slash}CLKO{slash}PCINT0)-Pad14)") (class "Default")
      (node (ref "IC4") (pin "14") (pinfunction "PB0(ICP1/CLKO/PCINT0)_14") (pintype "bidirectional"))
    )
    (net (code "229") (name "unconnected-(IC4-PD4(T0{slash}XCK{slash}PCINT20)-Pad6)") (class "Default")
      (node (ref "IC4") (pin "6") (pinfunction "PD4(T0/XCK/PCINT20)_6") (pintype "bidirectional"))
    )
    (net (code "230") (name "unconnected-(IC8A-QH*-Pad9)") (class "Default")
      (node (ref "IC8") (pin "9") (pinfunction "QH*_9") (pintype "tri_state"))
    )
    (net (code "231") (name "unconnected-(IC13A-CO-Pad12)") (class "Default")
      (node (ref "IC13") (pin "12") (pinfunction "CO_12") (pintype "output"))
    )
  )
)
